# iotst.net
KiCad netlist of a schematic drawn in EAGLE
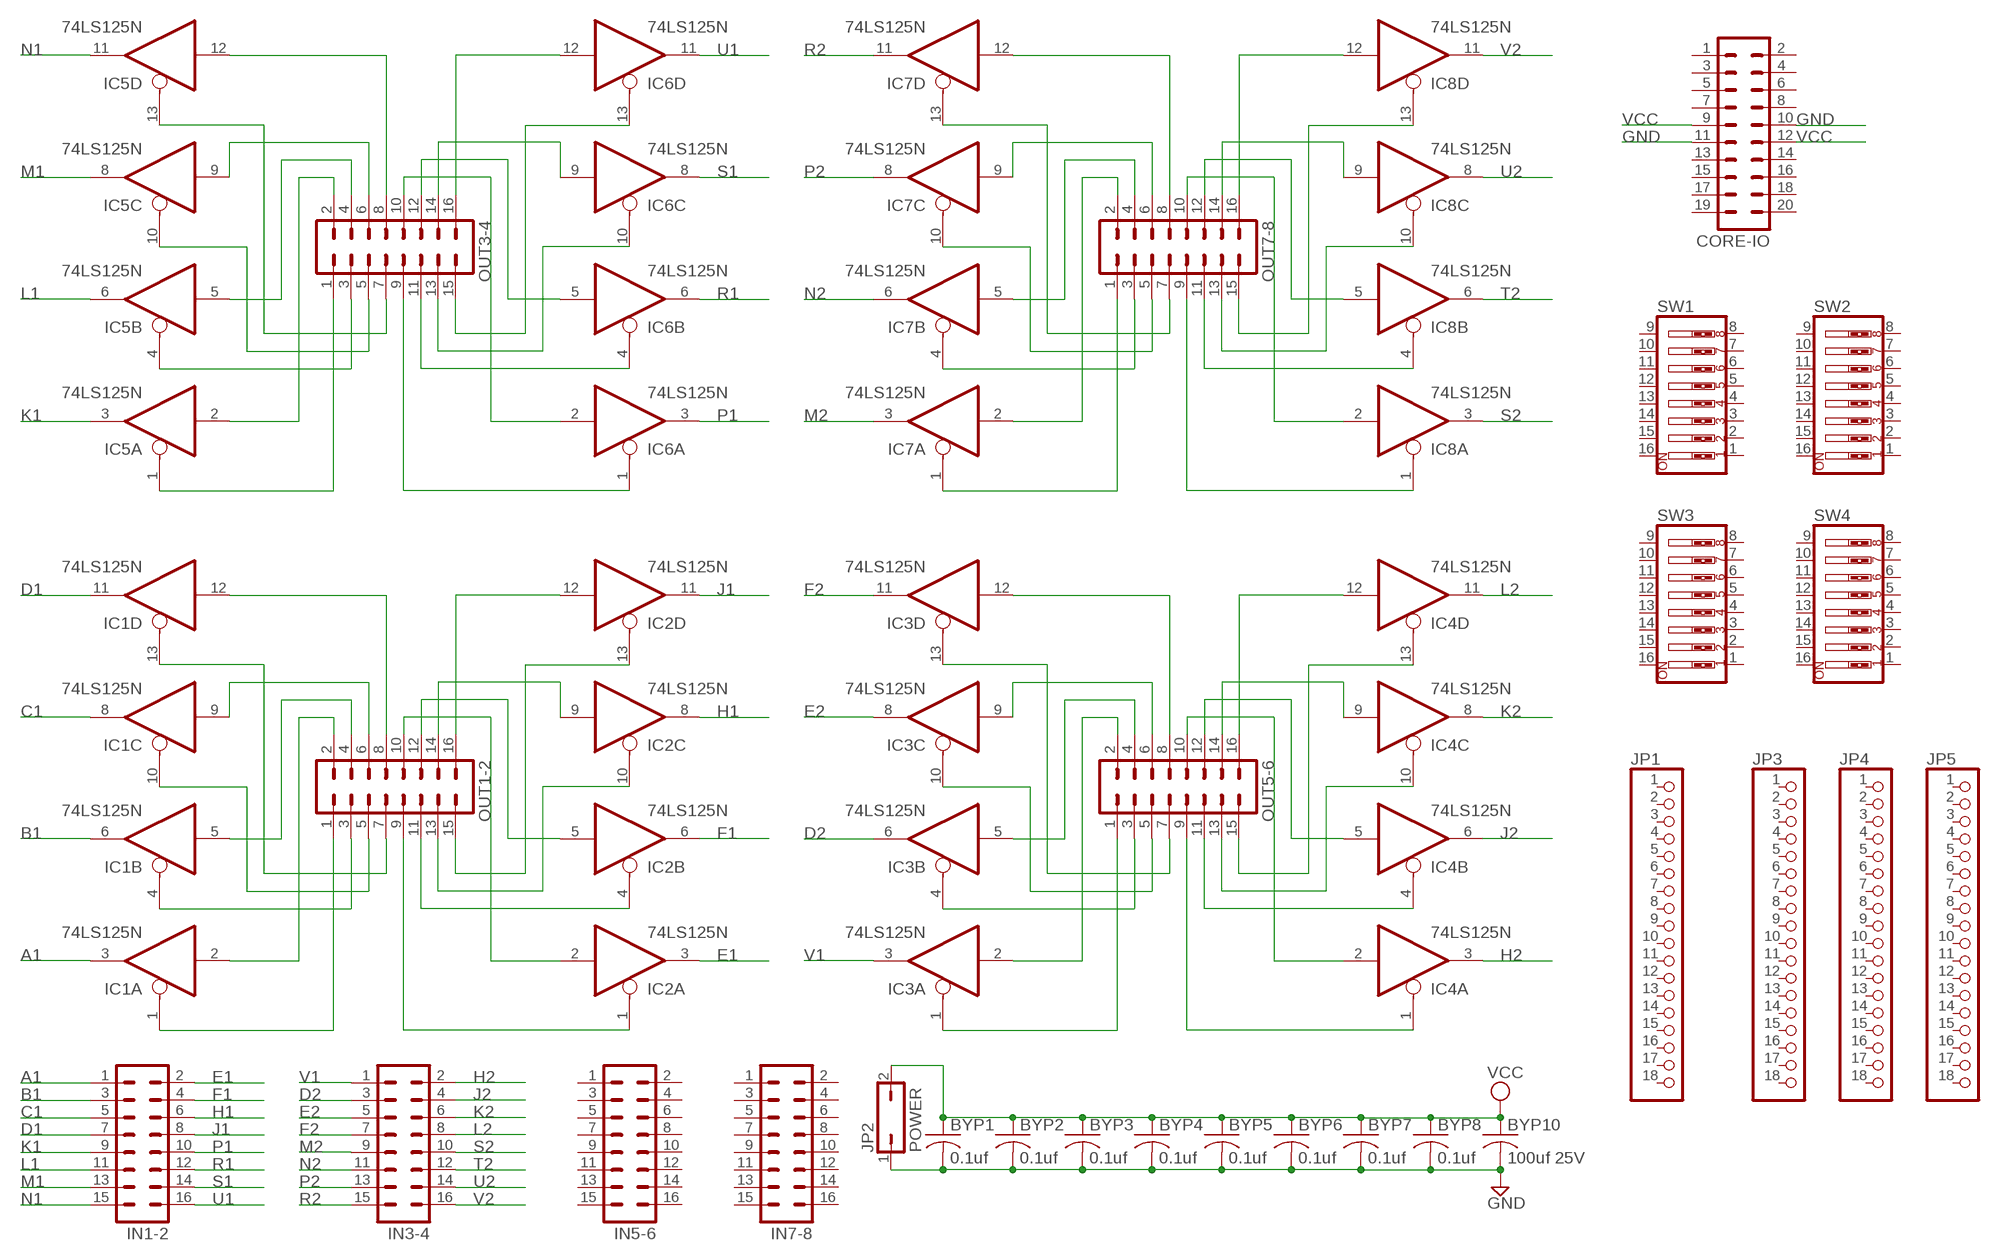
[diagram p0: schematic, sheet 1]
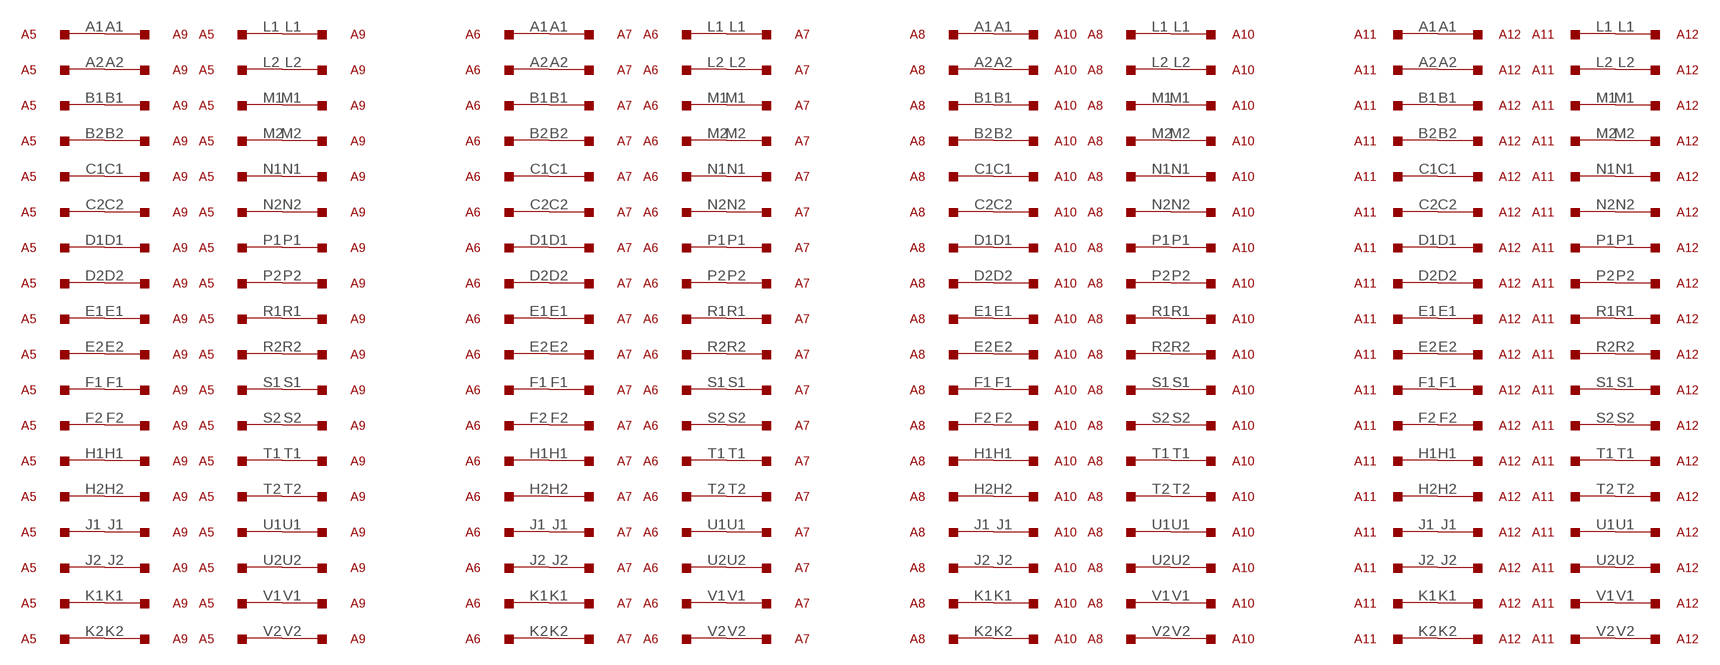
[diagram p1: schematic, sheet 2]
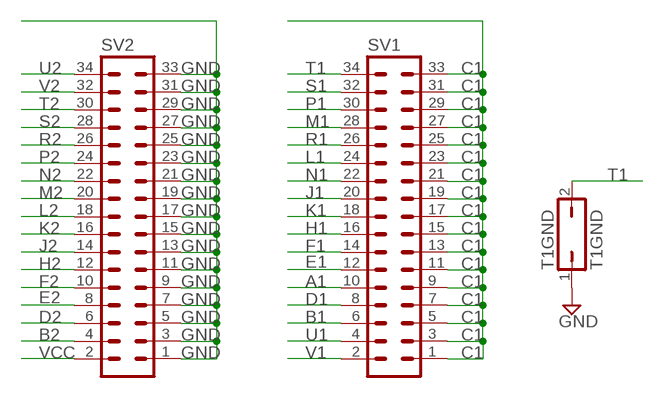
[diagram p2: schematic, sheet 3]

(export (version "E")
  (design (tool "Eeschema 10.0.6"))
  (components
    (comp (ref "A5")
      (value "M916")
      (footprint "eagle-import:H807")
      (libsource (lib "eagle-import") (part "M916"))
    )
    (comp (ref "A6")
      (value "M916")
      (footprint "eagle-import:H807")
      (libsource (lib "eagle-import") (part "M916"))
    )
    (comp (ref "A7")
      (value "M916")
      (footprint "eagle-import:H807")
      (libsource (lib "eagle-import") (part "M916"))
    )
    (comp (ref "A8")
      (value "M916")
      (footprint "eagle-import:H807")
      (libsource (lib "eagle-import") (part "M916"))
    )
    (comp (ref "A9")
      (value "M916")
      (footprint "eagle-import:H807")
      (libsource (lib "eagle-import") (part "M916"))
    )
    (comp (ref "A10")
      (value "M916")
      (footprint "eagle-import:H807")
      (libsource (lib "eagle-import") (part "M916"))
    )
    (comp (ref "A11")
      (value "M916")
      (footprint "eagle-import:H807")
      (libsource (lib "eagle-import") (part "M916"))
    )
    (comp (ref "A12")
      (value "M916")
      (footprint "eagle-import:H807")
      (libsource (lib "eagle-import") (part "M916"))
    )
    (comp (ref "BYP1")
      (value "0.1uf")
      (footprint "eagle-import:C050-025X075")
      (libsource (lib "eagle-import") (part "C-US050-025X075"))
    )
    (comp (ref "BYP2")
      (value "0.1uf")
      (footprint "eagle-import:C050-025X075")
      (libsource (lib "eagle-import") (part "C-US050-025X075"))
    )
    (comp (ref "BYP3")
      (value "0.1uf")
      (footprint "eagle-import:C050-025X075")
      (libsource (lib "eagle-import") (part "C-US050-025X075"))
    )
    (comp (ref "BYP4")
      (value "0.1uf")
      (footprint "eagle-import:C050-025X075")
      (libsource (lib "eagle-import") (part "C-US050-025X075"))
    )
    (comp (ref "BYP5")
      (value "0.1uf")
      (footprint "eagle-import:C050-025X075")
      (libsource (lib "eagle-import") (part "C-US050-025X075"))
    )
    (comp (ref "BYP6")
      (value "0.1uf")
      (footprint "eagle-import:C050-025X075")
      (libsource (lib "eagle-import") (part "C-US050-025X075"))
    )
    (comp (ref "BYP7")
      (value "0.1uf")
      (footprint "eagle-import:C050-025X075")
      (libsource (lib "eagle-import") (part "C-US050-025X075"))
    )
    (comp (ref "BYP8")
      (value "0.1uf")
      (footprint "eagle-import:C050-025X075")
      (libsource (lib "eagle-import") (part "C-US050-025X075"))
    )
    (comp (ref "BYP10")
      (value "100uf 25V")
      (footprint "eagle-import:C150-064X183")
      (libsource (lib "eagle-import") (part "C-US150-064X183"))
    )
    (comp (ref "CORE-IO")
      (value "MA10-2")
      (footprint "eagle-import:MA10-2")
      (libsource (lib "eagle-import") (part "MA10-2"))
    )
    (comp (ref "IC1")
      (value "74LS125N")
      (footprint "eagle-import:DIL14")
      (libsource (lib "eagle-import") (part "74125NLS"))
    )
    (comp (ref "IC2")
      (value "74LS125N")
      (footprint "eagle-import:DIL14")
      (libsource (lib "eagle-import") (part "74125NLS"))
    )
    (comp (ref "IC3")
      (value "74LS125N")
      (footprint "eagle-import:DIL14")
      (libsource (lib "eagle-import") (part "74125NLS"))
    )
    (comp (ref "IC4")
      (value "74LS125N")
      (footprint "eagle-import:DIL14")
      (libsource (lib "eagle-import") (part "74125NLS"))
    )
    (comp (ref "IC5")
      (value "74LS125N")
      (footprint "eagle-import:DIL14")
      (libsource (lib "eagle-import") (part "74125NLS"))
    )
    (comp (ref "IC6")
      (value "74LS125N")
      (footprint "eagle-import:DIL14")
      (libsource (lib "eagle-import") (part "74125NLS"))
    )
    (comp (ref "IC7")
      (value "74LS125N")
      (footprint "eagle-import:DIL14")
      (libsource (lib "eagle-import") (part "74125NLS"))
    )
    (comp (ref "IC8")
      (value "74LS125N")
      (footprint "eagle-import:DIL14")
      (libsource (lib "eagle-import") (part "74125NLS"))
    )
    (comp (ref "IN1-2")
      (value "MA08-2")
      (footprint "eagle-import:MA08-2")
      (libsource (lib "eagle-import") (part "MA08-2"))
    )
    (comp (ref "IN3-4")
      (value "MA08-2")
      (footprint "eagle-import:MA08-2")
      (libsource (lib "eagle-import") (part "MA08-2"))
    )
    (comp (ref "IN5-6")
      (value "MA08-2")
      (footprint "eagle-import:MA08-2")
      (libsource (lib "eagle-import") (part "MA08-2"))
    )
    (comp (ref "IN7-8")
      (value "MA08-2")
      (footprint "eagle-import:MA08-2")
      (libsource (lib "eagle-import") (part "MA08-2"))
    )
    (comp (ref "JP1")
      (value "PINHD-1X18")
      (footprint "eagle-import:1X18")
      (libsource (lib "eagle-import") (part "PINHD-1X18"))
    )
    (comp (ref "JP2")
      (value "POWER")
      (footprint "eagle-import:JP1")
      (libsource (lib "eagle-import") (part "JP1Q"))
    )
    (comp (ref "JP3")
      (value "PINHD-1X18")
      (footprint "eagle-import:1X18")
      (libsource (lib "eagle-import") (part "PINHD-1X18"))
    )
    (comp (ref "JP4")
      (value "PINHD-1X18")
      (footprint "eagle-import:1X18")
      (libsource (lib "eagle-import") (part "PINHD-1X18"))
    )
    (comp (ref "JP5")
      (value "PINHD-1X18")
      (footprint "eagle-import:1X18")
      (libsource (lib "eagle-import") (part "PINHD-1X18"))
    )
    (comp (ref "OUT1-2")
      (value "MA08-2")
      (footprint "eagle-import:MA08-2")
      (libsource (lib "eagle-import") (part "MA08-2"))
    )
    (comp (ref "OUT3-4")
      (value "MA08-2")
      (footprint "eagle-import:MA08-2")
      (libsource (lib "eagle-import") (part "MA08-2"))
    )
    (comp (ref "OUT5-6")
      (value "MA08-2")
      (footprint "eagle-import:MA08-2")
      (libsource (lib "eagle-import") (part "MA08-2"))
    )
    (comp (ref "OUT7-8")
      (value "MA08-2")
      (footprint "eagle-import:MA08-2")
      (libsource (lib "eagle-import") (part "MA08-2"))
    )
    (comp (ref "SW1")
      (value "SW_DIP-8")
      (footprint "eagle-import:EDG-08")
      (libsource (lib "eagle-import") (part "SW_DIP-8"))
    )
    (comp (ref "SW2")
      (value "SW_DIP-8")
      (footprint "eagle-import:EDG-08")
      (libsource (lib "eagle-import") (part "SW_DIP-8"))
    )
    (comp (ref "SW3")
      (value "SW_DIP-8")
      (footprint "eagle-import:EDG-08")
      (libsource (lib "eagle-import") (part "SW_DIP-8"))
    )
    (comp (ref "SW4")
      (value "SW_DIP-8")
      (footprint "eagle-import:EDG-08")
      (libsource (lib "eagle-import") (part "SW_DIP-8"))
    )
    (comp (ref "SV1")
      (value "MA17-2")
      (footprint "eagle-import:MA17-2")
      (libsource (lib "eagle-import") (part "MA17-2"))
    )
    (comp (ref "SV2")
      (value "MA17-2")
      (footprint "eagle-import:MA17-2")
      (libsource (lib "eagle-import") (part "MA17-2"))
    )
    (comp (ref "T1GND")
      (value "T1GND")
      (footprint "eagle-import:JP1")
      (libsource (lib "eagle-import") (part "JP1Q"))
    )
  )
  (nets
    (net (code "1") (name "A1") (class "Default")
      (node (ref "IC1") (pin "3") (pinfunction "O_3") (pintype "tri_state"))
      (node (ref "IN1-2") (pin "1") (pinfunction "1_1") (pintype "passive"))
      (node (ref "SV1") (pin "10") (pinfunction "10_10") (pintype "passive"))
    )
    (net (code "2") (name "B1") (class "Default")
      (node (ref "IC1") (pin "6") (pinfunction "O_6") (pintype "tri_state"))
      (node (ref "IN1-2") (pin "3") (pinfunction "3_3") (pintype "passive"))
      (node (ref "SV1") (pin "6") (pinfunction "6_6") (pintype "passive"))
    )
    (net (code "3") (name "B2") (class "Default")
      (node (ref "SV2") (pin "4") (pinfunction "4_4") (pintype "passive"))
    )
    (net (code "4") (name "C1") (class "Default")
      (node (ref "IC1") (pin "8") (pinfunction "O_8") (pintype "tri_state"))
      (node (ref "IN1-2") (pin "5") (pinfunction "5_5") (pintype "passive"))
      (node (ref "SV1") (pin "1") (pinfunction "1_1") (pintype "passive"))
      (node (ref "SV1") (pin "11") (pinfunction "11_11") (pintype "passive"))
      (node (ref "SV1") (pin "13") (pinfunction "13_13") (pintype "passive"))
      (node (ref "SV1") (pin "15") (pinfunction "15_15") (pintype "passive"))
      (node (ref "SV1") (pin "17") (pinfunction "17_17") (pintype "passive"))
      (node (ref "SV1") (pin "19") (pinfunction "19_19") (pintype "passive"))
      (node (ref "SV1") (pin "21") (pinfunction "21_21") (pintype "passive"))
      (node (ref "SV1") (pin "23") (pinfunction "23_23") (pintype "passive"))
      (node (ref "SV1") (pin "25") (pinfunction "25_25") (pintype "passive"))
      (node (ref "SV1") (pin "27") (pinfunction "27_27") (pintype "passive"))
      (node (ref "SV1") (pin "29") (pinfunction "29_29") (pintype "passive"))
      (node (ref "SV1") (pin "3") (pinfunction "3_3") (pintype "passive"))
      (node (ref "SV1") (pin "31") (pinfunction "31_31") (pintype "passive"))
      (node (ref "SV1") (pin "33") (pinfunction "33_33") (pintype "passive"))
      (node (ref "SV1") (pin "5") (pinfunction "5_5") (pintype "passive"))
      (node (ref "SV1") (pin "7") (pinfunction "7_7") (pintype "passive"))
      (node (ref "SV1") (pin "9") (pinfunction "9_9") (pintype "passive"))
    )
    (net (code "5") (name "D1") (class "Default")
      (node (ref "IC1") (pin "11") (pinfunction "O_11") (pintype "tri_state"))
      (node (ref "IN1-2") (pin "7") (pinfunction "7_7") (pintype "passive"))
      (node (ref "SV1") (pin "8") (pinfunction "8_8") (pintype "passive"))
    )
    (net (code "6") (name "D2") (class "Default")
      (node (ref "IC3") (pin "6") (pinfunction "O_6") (pintype "tri_state"))
      (node (ref "IN3-4") (pin "3") (pinfunction "3_3") (pintype "passive"))
      (node (ref "SV2") (pin "6") (pinfunction "6_6") (pintype "passive"))
    )
    (net (code "7") (name "E1") (class "Default")
      (node (ref "IC2") (pin "3") (pinfunction "O_3") (pintype "tri_state"))
      (node (ref "IN1-2") (pin "2") (pinfunction "2_2") (pintype "passive"))
      (node (ref "SV1") (pin "12") (pinfunction "12_12") (pintype "passive"))
    )
    (net (code "8") (name "E2") (class "Default")
      (node (ref "IC3") (pin "8") (pinfunction "O_8") (pintype "tri_state"))
      (node (ref "IN3-4") (pin "5") (pinfunction "5_5") (pintype "passive"))
      (node (ref "SV2") (pin "8") (pinfunction "8_8") (pintype "passive"))
    )
    (net (code "9") (name "F1") (class "Default")
      (node (ref "IC2") (pin "6") (pinfunction "O_6") (pintype "tri_state"))
      (node (ref "IN1-2") (pin "4") (pinfunction "4_4") (pintype "passive"))
      (node (ref "SV1") (pin "14") (pinfunction "14_14") (pintype "passive"))
    )
    (net (code "10") (name "F2") (class "Default")
      (node (ref "IC3") (pin "11") (pinfunction "O_11") (pintype "tri_state"))
      (node (ref "IN3-4") (pin "7") (pinfunction "7_7") (pintype "passive"))
      (node (ref "SV2") (pin "10") (pinfunction "10_10") (pintype "passive"))
    )
    (net (code "11") (name "GND") (class "Default")
      (node (ref "BYP1") (pin "2") (pinfunction "2_2") (pintype "passive"))
      (node (ref "BYP10") (pin "2") (pinfunction "2_2") (pintype "passive"))
      (node (ref "BYP2") (pin "2") (pinfunction "2_2") (pintype "passive"))
      (node (ref "BYP3") (pin "2") (pinfunction "2_2") (pintype "passive"))
      (node (ref "BYP4") (pin "2") (pinfunction "2_2") (pintype "passive"))
      (node (ref "BYP5") (pin "2") (pinfunction "2_2") (pintype "passive"))
      (node (ref "BYP6") (pin "2") (pinfunction "2_2") (pintype "passive"))
      (node (ref "BYP7") (pin "2") (pinfunction "2_2") (pintype "passive"))
      (node (ref "BYP8") (pin "2") (pinfunction "2_2") (pintype "passive"))
      (node (ref "CORE-IO") (pin "10") (pinfunction "10_10") (pintype "passive"))
      (node (ref "CORE-IO") (pin "11") (pinfunction "11_11") (pintype "passive"))
      (node (ref "JP2") (pin "1") (pinfunction "1_1") (pintype "passive"))
      (node (ref "SV2") (pin "1") (pinfunction "1_1") (pintype "passive"))
      (node (ref "SV2") (pin "11") (pinfunction "11_11") (pintype "passive"))
      (node (ref "SV2") (pin "13") (pinfunction "13_13") (pintype "passive"))
      (node (ref "SV2") (pin "15") (pinfunction "15_15") (pintype "passive"))
      (node (ref "SV2") (pin "17") (pinfunction "17_17") (pintype "passive"))
      (node (ref "SV2") (pin "19") (pinfunction "19_19") (pintype "passive"))
      (node (ref "SV2") (pin "21") (pinfunction "21_21") (pintype "passive"))
      (node (ref "SV2") (pin "23") (pinfunction "23_23") (pintype "passive"))
      (node (ref "SV2") (pin "25") (pinfunction "25_25") (pintype "passive"))
      (node (ref "SV2") (pin "27") (pinfunction "27_27") (pintype "passive"))
      (node (ref "SV2") (pin "29") (pinfunction "29_29") (pintype "passive"))
      (node (ref "SV2") (pin "3") (pinfunction "3_3") (pintype "passive"))
      (node (ref "SV2") (pin "31") (pinfunction "31_31") (pintype "passive"))
      (node (ref "SV2") (pin "33") (pinfunction "33_33") (pintype "passive"))
      (node (ref "SV2") (pin "5") (pinfunction "5_5") (pintype "passive"))
      (node (ref "SV2") (pin "7") (pinfunction "7_7") (pintype "passive"))
      (node (ref "SV2") (pin "9") (pinfunction "9_9") (pintype "passive"))
      (node (ref "T1GND") (pin "1") (pinfunction "1_1") (pintype "passive"))
    )
    (net (code "12") (name "H1") (class "Default")
      (node (ref "IC2") (pin "8") (pinfunction "O_8") (pintype "tri_state"))
      (node (ref "IN1-2") (pin "6") (pinfunction "6_6") (pintype "passive"))
      (node (ref "SV1") (pin "16") (pinfunction "16_16") (pintype "passive"))
    )
    (net (code "13") (name "H2") (class "Default")
      (node (ref "IC4") (pin "3") (pinfunction "O_3") (pintype "tri_state"))
      (node (ref "IN3-4") (pin "2") (pinfunction "2_2") (pintype "passive"))
      (node (ref "SV2") (pin "12") (pinfunction "12_12") (pintype "passive"))
    )
    (net (code "14") (name "J1") (class "Default")
      (node (ref "IC2") (pin "11") (pinfunction "O_11") (pintype "tri_state"))
      (node (ref "IN1-2") (pin "8") (pinfunction "8_8") (pintype "passive"))
      (node (ref "SV1") (pin "20") (pinfunction "20_20") (pintype "passive"))
    )
    (net (code "15") (name "J2") (class "Default")
      (node (ref "IC4") (pin "6") (pinfunction "O_6") (pintype "tri_state"))
      (node (ref "IN3-4") (pin "4") (pinfunction "4_4") (pintype "passive"))
      (node (ref "SV2") (pin "14") (pinfunction "14_14") (pintype "passive"))
    )
    (net (code "16") (name "K1") (class "Default")
      (node (ref "IC5") (pin "3") (pinfunction "O_3") (pintype "tri_state"))
      (node (ref "IN1-2") (pin "9") (pinfunction "9_9") (pintype "passive"))
      (node (ref "SV1") (pin "18") (pinfunction "18_18") (pintype "passive"))
    )
    (net (code "17") (name "K2") (class "Default")
      (node (ref "IC4") (pin "8") (pinfunction "O_8") (pintype "tri_state"))
      (node (ref "IN3-4") (pin "6") (pinfunction "6_6") (pintype "passive"))
      (node (ref "SV2") (pin "16") (pinfunction "16_16") (pintype "passive"))
    )
    (net (code "18") (name "L1") (class "Default")
      (node (ref "IC5") (pin "6") (pinfunction "O_6") (pintype "tri_state"))
      (node (ref "IN1-2") (pin "11") (pinfunction "11_11") (pintype "passive"))
      (node (ref "SV1") (pin "24") (pinfunction "24_24") (pintype "passive"))
    )
    (net (code "19") (name "L2") (class "Default")
      (node (ref "IC4") (pin "11") (pinfunction "O_11") (pintype "tri_state"))
      (node (ref "IN3-4") (pin "8") (pinfunction "8_8") (pintype "passive"))
      (node (ref "SV2") (pin "18") (pinfunction "18_18") (pintype "passive"))
    )
    (net (code "20") (name "M1") (class "Default")
      (node (ref "IC5") (pin "8") (pinfunction "O_8") (pintype "tri_state"))
      (node (ref "IN1-2") (pin "13") (pinfunction "13_13") (pintype "passive"))
      (node (ref "SV1") (pin "28") (pinfunction "28_28") (pintype "passive"))
    )
    (net (code "21") (name "M2") (class "Default")
      (node (ref "IC7") (pin "3") (pinfunction "O_3") (pintype "tri_state"))
      (node (ref "IN3-4") (pin "9") (pinfunction "9_9") (pintype "passive"))
      (node (ref "SV2") (pin "20") (pinfunction "20_20") (pintype "passive"))
    )
    (net (code "22") (name "N1") (class "Default")
      (node (ref "IC5") (pin "11") (pinfunction "O_11") (pintype "tri_state"))
      (node (ref "IN1-2") (pin "15") (pinfunction "15_15") (pintype "passive"))
      (node (ref "SV1") (pin "22") (pinfunction "22_22") (pintype "passive"))
    )
    (net (code "23") (name "N2") (class "Default")
      (node (ref "IC7") (pin "6") (pinfunction "O_6") (pintype "tri_state"))
      (node (ref "IN3-4") (pin "11") (pinfunction "11_11") (pintype "passive"))
      (node (ref "SV2") (pin "22") (pinfunction "22_22") (pintype "passive"))
    )
    (net (code "24") (name "Net-(A5A-P$2)") (class "Default")
      (node (ref "A5") (pin "A1") (pinfunction "P$2_A1") (pintype "bidirectional"))
      (node (ref "A9") (pin "A1") (pinfunction "P$2_A1") (pintype "bidirectional"))
    )
    (net (code "25") (name "Net-(A5AA-P$2)") (class "Default")
      (node (ref "A5") (pin "R1") (pinfunction "P$2_R1") (pintype "bidirectional"))
      (node (ref "A9") (pin "R1") (pinfunction "P$2_R1") (pintype "bidirectional"))
    )
    (net (code "26") (name "Net-(A5AB-P$2)") (class "Default")
      (node (ref "A5") (pin "R2") (pinfunction "P$2_R2") (pintype "bidirectional"))
      (node (ref "A9") (pin "R2") (pinfunction "P$2_R2") (pintype "bidirectional"))
    )
    (net (code "27") (name "Net-(A5AC-P$2)") (class "Default")
      (node (ref "A5") (pin "S1") (pinfunction "P$2_S1") (pintype "bidirectional"))
      (node (ref "A9") (pin "S1") (pinfunction "P$2_S1") (pintype "bidirectional"))
    )
    (net (code "28") (name "Net-(A5AD-P$2)") (class "Default")
      (node (ref "A5") (pin "S2") (pinfunction "P$2_S2") (pintype "bidirectional"))
      (node (ref "A9") (pin "S2") (pinfunction "P$2_S2") (pintype "bidirectional"))
    )
    (net (code "29") (name "Net-(A5AE-P$2)") (class "Default")
      (node (ref "A5") (pin "T1") (pinfunction "P$2_T1") (pintype "bidirectional"))
      (node (ref "A9") (pin "T1") (pinfunction "P$2_T1") (pintype "bidirectional"))
    )
    (net (code "30") (name "Net-(A5AF-P$2)") (class "Default")
      (node (ref "A5") (pin "T2") (pinfunction "P$2_T2") (pintype "bidirectional"))
      (node (ref "A9") (pin "T2") (pinfunction "P$2_T2") (pintype "bidirectional"))
    )
    (net (code "31") (name "Net-(A5AG-P$2)") (class "Default")
      (node (ref "A5") (pin "U1") (pinfunction "P$2_U1") (pintype "bidirectional"))
      (node (ref "A9") (pin "U1") (pinfunction "P$2_U1") (pintype "bidirectional"))
    )
    (net (code "32") (name "Net-(A5AH-P$2)") (class "Default")
      (node (ref "A5") (pin "U2") (pinfunction "P$2_U2") (pintype "bidirectional"))
      (node (ref "A9") (pin "U2") (pinfunction "P$2_U2") (pintype "bidirectional"))
    )
    (net (code "33") (name "Net-(A5AI-P$2)") (class "Default")
      (node (ref "A5") (pin "V1") (pinfunction "P$2_V1") (pintype "bidirectional"))
      (node (ref "A9") (pin "V1") (pinfunction "P$2_V1") (pintype "bidirectional"))
    )
    (net (code "34") (name "Net-(A5AJ-P$2)") (class "Default")
      (node (ref "A5") (pin "V2") (pinfunction "P$2_V2") (pintype "bidirectional"))
      (node (ref "A9") (pin "V2") (pinfunction "P$2_V2") (pintype "bidirectional"))
    )
    (net (code "35") (name "Net-(A5B-P$2)") (class "Default")
      (node (ref "A5") (pin "A2") (pinfunction "P$2_A2") (pintype "bidirectional"))
      (node (ref "A9") (pin "A2") (pinfunction "P$2_A2") (pintype "bidirectional"))
    )
    (net (code "36") (name "Net-(A5C-P$2)") (class "Default")
      (node (ref "A5") (pin "B1") (pinfunction "P$2_B1") (pintype "bidirectional"))
      (node (ref "A9") (pin "B1") (pinfunction "P$2_B1") (pintype "bidirectional"))
    )
    (net (code "37") (name "Net-(A5D-P$2)") (class "Default")
      (node (ref "A5") (pin "B2") (pinfunction "P$2_B2") (pintype "bidirectional"))
      (node (ref "A9") (pin "B2") (pinfunction "P$2_B2") (pintype "bidirectional"))
    )
    (net (code "38") (name "Net-(A5E-P$2)") (class "Default")
      (node (ref "A5") (pin "C1") (pinfunction "P$2_C1") (pintype "bidirectional"))
      (node (ref "A9") (pin "C1") (pinfunction "P$2_C1") (pintype "bidirectional"))
    )
    (net (code "39") (name "Net-(A5F-P$2)") (class "Default")
      (node (ref "A5") (pin "C2") (pinfunction "P$2_C2") (pintype "bidirectional"))
      (node (ref "A9") (pin "C2") (pinfunction "P$2_C2") (pintype "bidirectional"))
    )
    (net (code "40") (name "Net-(A5G-P$2)") (class "Default")
      (node (ref "A5") (pin "D1") (pinfunction "P$2_D1") (pintype "bidirectional"))
      (node (ref "A9") (pin "D1") (pinfunction "P$2_D1") (pintype "bidirectional"))
    )
    (net (code "41") (name "Net-(A5H-P$2)") (class "Default")
      (node (ref "A5") (pin "D2") (pinfunction "P$2_D2") (pintype "bidirectional"))
      (node (ref "A9") (pin "D2") (pinfunction "P$2_D2") (pintype "bidirectional"))
    )
    (net (code "42") (name "Net-(A5I-P$2)") (class "Default")
      (node (ref "A5") (pin "E1") (pinfunction "P$2_E1") (pintype "bidirectional"))
      (node (ref "A9") (pin "E1") (pinfunction "P$2_E1") (pintype "bidirectional"))
    )
    (net (code "43") (name "Net-(A5J-P$2)") (class "Default")
      (node (ref "A5") (pin "E2") (pinfunction "P$2_E2") (pintype "bidirectional"))
      (node (ref "A9") (pin "E2") (pinfunction "P$2_E2") (pintype "bidirectional"))
    )
    (net (code "44") (name "Net-(A5K-P$2)") (class "Default")
      (node (ref "A5") (pin "F1") (pinfunction "P$2_F1") (pintype "bidirectional"))
      (node (ref "A9") (pin "F1") (pinfunction "P$2_F1") (pintype "bidirectional"))
    )
    (net (code "45") (name "Net-(A5L-P$2)") (class "Default")
      (node (ref "A5") (pin "F2") (pinfunction "P$2_F2") (pintype "bidirectional"))
      (node (ref "A9") (pin "F2") (pinfunction "P$2_F2") (pintype "bidirectional"))
    )
    (net (code "46") (name "Net-(A5M-P$2)") (class "Default")
      (node (ref "A5") (pin "H1") (pinfunction "P$2_H1") (pintype "bidirectional"))
      (node (ref "A9") (pin "H1") (pinfunction "P$2_H1") (pintype "bidirectional"))
    )
    (net (code "47") (name "Net-(A5N-P$2)") (class "Default")
      (node (ref "A5") (pin "H2") (pinfunction "P$2_H2") (pintype "bidirectional"))
      (node (ref "A9") (pin "H2") (pinfunction "P$2_H2") (pintype "bidirectional"))
    )
    (net (code "48") (name "Net-(A5O-P$2)") (class "Default")
      (node (ref "A5") (pin "J1") (pinfunction "P$2_J1") (pintype "bidirectional"))
      (node (ref "A9") (pin "J1") (pinfunction "P$2_J1") (pintype "bidirectional"))
    )
    (net (code "49") (name "Net-(A5P-P$2)") (class "Default")
      (node (ref "A5") (pin "J2") (pinfunction "P$2_J2") (pintype "bidirectional"))
      (node (ref "A9") (pin "J2") (pinfunction "P$2_J2") (pintype "bidirectional"))
    )
    (net (code "50") (name "Net-(A5Q-P$2)") (class "Default")
      (node (ref "A5") (pin "K1") (pinfunction "P$2_K1") (pintype "bidirectional"))
      (node (ref "A9") (pin "K1") (pinfunction "P$2_K1") (pintype "bidirectional"))
    )
    (net (code "51") (name "Net-(A5R-P$2)") (class "Default")
      (node (ref "A5") (pin "K2") (pinfunction "P$2_K2") (pintype "bidirectional"))
      (node (ref "A9") (pin "K2") (pinfunction "P$2_K2") (pintype "bidirectional"))
    )
    (net (code "52") (name "Net-(A5S-P$2)") (class "Default")
      (node (ref "A5") (pin "L1") (pinfunction "P$2_L1") (pintype "bidirectional"))
      (node (ref "A9") (pin "L1") (pinfunction "P$2_L1") (pintype "bidirectional"))
    )
    (net (code "53") (name "Net-(A5T-P$2)") (class "Default")
      (node (ref "A5") (pin "L2") (pinfunction "P$2_L2") (pintype "bidirectional"))
      (node (ref "A9") (pin "L2") (pinfunction "P$2_L2") (pintype "bidirectional"))
    )
    (net (code "54") (name "Net-(A5U-P$2)") (class "Default")
      (node (ref "A5") (pin "M1") (pinfunction "P$2_M1") (pintype "bidirectional"))
      (node (ref "A9") (pin "M1") (pinfunction "P$2_M1") (pintype "bidirectional"))
    )
    (net (code "55") (name "Net-(A5V-P$2)") (class "Default")
      (node (ref "A5") (pin "M2") (pinfunction "P$2_M2") (pintype "bidirectional"))
      (node (ref "A9") (pin "M2") (pinfunction "P$2_M2") (pintype "bidirectional"))
    )
    (net (code "56") (name "Net-(A5W-P$2)") (class "Default")
      (node (ref "A5") (pin "N1") (pinfunction "P$2_N1") (pintype "bidirectional"))
      (node (ref "A9") (pin "N1") (pinfunction "P$2_N1") (pintype "bidirectional"))
    )
    (net (code "57") (name "Net-(A5X-P$2)") (class "Default")
      (node (ref "A5") (pin "N2") (pinfunction "P$2_N2") (pintype "bidirectional"))
      (node (ref "A9") (pin "N2") (pinfunction "P$2_N2") (pintype "bidirectional"))
    )
    (net (code "58") (name "Net-(A5Y-P$2)") (class "Default")
      (node (ref "A5") (pin "P1") (pinfunction "P$2_P1") (pintype "bidirectional"))
      (node (ref "A9") (pin "P1") (pinfunction "P$2_P1") (pintype "bidirectional"))
    )
    (net (code "59") (name "Net-(A5Z-P$2)") (class "Default")
      (node (ref "A5") (pin "P2") (pinfunction "P$2_P2") (pintype "bidirectional"))
      (node (ref "A9") (pin "P2") (pinfunction "P$2_P2") (pintype "bidirectional"))
    )
    (net (code "60") (name "Net-(A6A-P$2)") (class "Default")
      (node (ref "A6") (pin "A1") (pinfunction "P$2_A1") (pintype "bidirectional"))
      (node (ref "A7") (pin "A1") (pinfunction "P$2_A1") (pintype "bidirectional"))
    )
    (net (code "61") (name "Net-(A6AA-P$2)") (class "Default")
      (node (ref "A6") (pin "R1") (pinfunction "P$2_R1") (pintype "bidirectional"))
      (node (ref "A7") (pin "R1") (pinfunction "P$2_R1") (pintype "bidirectional"))
    )
    (net (code "62") (name "Net-(A6AB-P$2)") (class "Default")
      (node (ref "A6") (pin "R2") (pinfunction "P$2_R2") (pintype "bidirectional"))
      (node (ref "A7") (pin "R2") (pinfunction "P$2_R2") (pintype "bidirectional"))
    )
    (net (code "63") (name "Net-(A6AC-P$2)") (class "Default")
      (node (ref "A6") (pin "S1") (pinfunction "P$2_S1") (pintype "bidirectional"))
      (node (ref "A7") (pin "S1") (pinfunction "P$2_S1") (pintype "bidirectional"))
    )
    (net (code "64") (name "Net-(A6AD-P$2)") (class "Default")
      (node (ref "A6") (pin "S2") (pinfunction "P$2_S2") (pintype "bidirectional"))
      (node (ref "A7") (pin "S2") (pinfunction "P$2_S2") (pintype "bidirectional"))
    )
    (net (code "65") (name "Net-(A6AE-P$2)") (class "Default")
      (node (ref "A6") (pin "T1") (pinfunction "P$2_T1") (pintype "bidirectional"))
      (node (ref "A7") (pin "T1") (pinfunction "P$2_T1") (pintype "bidirectional"))
    )
    (net (code "66") (name "Net-(A6AF-P$2)") (class "Default")
      (node (ref "A6") (pin "T2") (pinfunction "P$2_T2") (pintype "bidirectional"))
      (node (ref "A7") (pin "T2") (pinfunction "P$2_T2") (pintype "bidirectional"))
    )
    (net (code "67") (name "Net-(A6AG-P$2)") (class "Default")
      (node (ref "A6") (pin "U1") (pinfunction "P$2_U1") (pintype "bidirectional"))
      (node (ref "A7") (pin "U1") (pinfunction "P$2_U1") (pintype "bidirectional"))
    )
    (net (code "68") (name "Net-(A6AH-P$2)") (class "Default")
      (node (ref "A6") (pin "U2") (pinfunction "P$2_U2") (pintype "bidirectional"))
      (node (ref "A7") (pin "U2") (pinfunction "P$2_U2") (pintype "bidirectional"))
    )
    (net (code "69") (name "Net-(A6AI-P$2)") (class "Default")
      (node (ref "A6") (pin "V1") (pinfunction "P$2_V1") (pintype "bidirectional"))
      (node (ref "A7") (pin "V1") (pinfunction "P$2_V1") (pintype "bidirectional"))
    )
    (net (code "70") (name "Net-(A6AJ-P$2)") (class "Default")
      (node (ref "A6") (pin "V2") (pinfunction "P$2_V2") (pintype "bidirectional"))
      (node (ref "A7") (pin "V2") (pinfunction "P$2_V2") (pintype "bidirectional"))
    )
    (net (code "71") (name "Net-(A6B-P$2)") (class "Default")
      (node (ref "A6") (pin "A2") (pinfunction "P$2_A2") (pintype "bidirectional"))
      (node (ref "A7") (pin "A2") (pinfunction "P$2_A2") (pintype "bidirectional"))
    )
    (net (code "72") (name "Net-(A6C-P$2)") (class "Default")
      (node (ref "A6") (pin "B1") (pinfunction "P$2_B1") (pintype "bidirectional"))
      (node (ref "A7") (pin "B1") (pinfunction "P$2_B1") (pintype "bidirectional"))
    )
    (net (code "73") (name "Net-(A6D-P$2)") (class "Default")
      (node (ref "A6") (pin "B2") (pinfunction "P$2_B2") (pintype "bidirectional"))
      (node (ref "A7") (pin "B2") (pinfunction "P$2_B2") (pintype "bidirectional"))
    )
    (net (code "74") (name "Net-(A6E-P$2)") (class "Default")
      (node (ref "A6") (pin "C1") (pinfunction "P$2_C1") (pintype "bidirectional"))
      (node (ref "A7") (pin "C1") (pinfunction "P$2_C1") (pintype "bidirectional"))
    )
    (net (code "75") (name "Net-(A6F-P$2)") (class "Default")
      (node (ref "A6") (pin "C2") (pinfunction "P$2_C2") (pintype "bidirectional"))
      (node (ref "A7") (pin "C2") (pinfunction "P$2_C2") (pintype "bidirectional"))
    )
    (net (code "76") (name "Net-(A6G-P$2)") (class "Default")
      (node (ref "A6") (pin "D1") (pinfunction "P$2_D1") (pintype "bidirectional"))
      (node (ref "A7") (pin "D1") (pinfunction "P$2_D1") (pintype "bidirectional"))
    )
    (net (code "77") (name "Net-(A6H-P$2)") (class "Default")
      (node (ref "A6") (pin "D2") (pinfunction "P$2_D2") (pintype "bidirectional"))
      (node (ref "A7") (pin "D2") (pinfunction "P$2_D2") (pintype "bidirectional"))
    )
    (net (code "78") (name "Net-(A6I-P$2)") (class "Default")
      (node (ref "A6") (pin "E1") (pinfunction "P$2_E1") (pintype "bidirectional"))
      (node (ref "A7") (pin "E1") (pinfunction "P$2_E1") (pintype "bidirectional"))
    )
    (net (code "79") (name "Net-(A6J-P$2)") (class "Default")
      (node (ref "A6") (pin "E2") (pinfunction "P$2_E2") (pintype "bidirectional"))
      (node (ref "A7") (pin "E2") (pinfunction "P$2_E2") (pintype "bidirectional"))
    )
    (net (code "80") (name "Net-(A6K-P$2)") (class "Default")
      (node (ref "A6") (pin "F1") (pinfunction "P$2_F1") (pintype "bidirectional"))
      (node (ref "A7") (pin "F1") (pinfunction "P$2_F1") (pintype "bidirectional"))
    )
    (net (code "81") (name "Net-(A6L-P$2)") (class "Default")
      (node (ref "A6") (pin "F2") (pinfunction "P$2_F2") (pintype "bidirectional"))
      (node (ref "A7") (pin "F2") (pinfunction "P$2_F2") (pintype "bidirectional"))
    )
    (net (code "82") (name "Net-(A6M-P$2)") (class "Default")
      (node (ref "A6") (pin "H1") (pinfunction "P$2_H1") (pintype "bidirectional"))
      (node (ref "A7") (pin "H1") (pinfunction "P$2_H1") (pintype "bidirectional"))
    )
    (net (code "83") (name "Net-(A6N-P$2)") (class "Default")
      (node (ref "A6") (pin "H2") (pinfunction "P$2_H2") (pintype "bidirectional"))
      (node (ref "A7") (pin "H2") (pinfunction "P$2_H2") (pintype "bidirectional"))
    )
    (net (code "84") (name "Net-(A6O-P$2)") (class "Default")
      (node (ref "A6") (pin "J1") (pinfunction "P$2_J1") (pintype "bidirectional"))
      (node (ref "A7") (pin "J1") (pinfunction "P$2_J1") (pintype "bidirectional"))
    )
    (net (code "85") (name "Net-(A6P-P$2)") (class "Default")
      (node (ref "A6") (pin "J2") (pinfunction "P$2_J2") (pintype "bidirectional"))
      (node (ref "A7") (pin "J2") (pinfunction "P$2_J2") (pintype "bidirectional"))
    )
    (net (code "86") (name "Net-(A6Q-P$2)") (class "Default")
      (node (ref "A6") (pin "K1") (pinfunction "P$2_K1") (pintype "bidirectional"))
      (node (ref "A7") (pin "K1") (pinfunction "P$2_K1") (pintype "bidirectional"))
    )
    (net (code "87") (name "Net-(A6R-P$2)") (class "Default")
      (node (ref "A6") (pin "K2") (pinfunction "P$2_K2") (pintype "bidirectional"))
      (node (ref "A7") (pin "K2") (pinfunction "P$2_K2") (pintype "bidirectional"))
    )
    (net (code "88") (name "Net-(A6S-P$2)") (class "Default")
      (node (ref "A6") (pin "L1") (pinfunction "P$2_L1") (pintype "bidirectional"))
      (node (ref "A7") (pin "L1") (pinfunction "P$2_L1") (pintype "bidirectional"))
    )
    (net (code "89") (name "Net-(A6T-P$2)") (class "Default")
      (node (ref "A6") (pin "L2") (pinfunction "P$2_L2") (pintype "bidirectional"))
      (node (ref "A7") (pin "L2") (pinfunction "P$2_L2") (pintype "bidirectional"))
    )
    (net (code "90") (name "Net-(A6U-P$2)") (class "Default")
      (node (ref "A6") (pin "M1") (pinfunction "P$2_M1") (pintype "bidirectional"))
      (node (ref "A7") (pin "M1") (pinfunction "P$2_M1") (pintype "bidirectional"))
    )
    (net (code "91") (name "Net-(A6V-P$2)") (class "Default")
      (node (ref "A6") (pin "M2") (pinfunction "P$2_M2") (pintype "bidirectional"))
      (node (ref "A7") (pin "M2") (pinfunction "P$2_M2") (pintype "bidirectional"))
    )
    (net (code "92") (name "Net-(A6W-P$2)") (class "Default")
      (node (ref "A6") (pin "N1") (pinfunction "P$2_N1") (pintype "bidirectional"))
      (node (ref "A7") (pin "N1") (pinfunction "P$2_N1") (pintype "bidirectional"))
    )
    (net (code "93") (name "Net-(A6X-P$2)") (class "Default")
      (node (ref "A6") (pin "N2") (pinfunction "P$2_N2") (pintype "bidirectional"))
      (node (ref "A7") (pin "N2") (pinfunction "P$2_N2") (pintype "bidirectional"))
    )
    (net (code "94") (name "Net-(A6Y-P$2)") (class "Default")
      (node (ref "A6") (pin "P1") (pinfunction "P$2_P1") (pintype "bidirectional"))
      (node (ref "A7") (pin "P1") (pinfunction "P$2_P1") (pintype "bidirectional"))
    )
    (net (code "95") (name "Net-(A6Z-P$2)") (class "Default")
      (node (ref "A6") (pin "P2") (pinfunction "P$2_P2") (pintype "bidirectional"))
      (node (ref "A7") (pin "P2") (pinfunction "P$2_P2") (pintype "bidirectional"))
    )
    (net (code "96") (name "Net-(A10A-P$2)") (class "Default")
      (node (ref "A10") (pin "A1") (pinfunction "P$2_A1") (pintype "bidirectional"))
      (node (ref "A8") (pin "A1") (pinfunction "P$2_A1") (pintype "bidirectional"))
    )
    (net (code "97") (name "Net-(A10AA-P$2)") (class "Default")
      (node (ref "A10") (pin "R1") (pinfunction "P$2_R1") (pintype "bidirectional"))
      (node (ref "A8") (pin "R1") (pinfunction "P$2_R1") (pintype "bidirectional"))
    )
    (net (code "98") (name "Net-(A10AB-P$2)") (class "Default")
      (node (ref "A10") (pin "R2") (pinfunction "P$2_R2") (pintype "bidirectional"))
      (node (ref "A8") (pin "R2") (pinfunction "P$2_R2") (pintype "bidirectional"))
    )
    (net (code "99") (name "Net-(A10AC-P$2)") (class "Default")
      (node (ref "A10") (pin "S1") (pinfunction "P$2_S1") (pintype "bidirectional"))
      (node (ref "A8") (pin "S1") (pinfunction "P$2_S1") (pintype "bidirectional"))
    )
    (net (code "100") (name "Net-(A10AD-P$2)") (class "Default")
      (node (ref "A10") (pin "S2") (pinfunction "P$2_S2") (pintype "bidirectional"))
      (node (ref "A8") (pin "S2") (pinfunction "P$2_S2") (pintype "bidirectional"))
    )
    (net (code "101") (name "Net-(A10AE-P$2)") (class "Default")
      (node (ref "A10") (pin "T1") (pinfunction "P$2_T1") (pintype "bidirectional"))
      (node (ref "A8") (pin "T1") (pinfunction "P$2_T1") (pintype "bidirectional"))
    )
    (net (code "102") (name "Net-(A10AF-P$2)") (class "Default")
      (node (ref "A10") (pin "T2") (pinfunction "P$2_T2") (pintype "bidirectional"))
      (node (ref "A8") (pin "T2") (pinfunction "P$2_T2") (pintype "bidirectional"))
    )
    (net (code "103") (name "Net-(A10AG-P$2)") (class "Default")
      (node (ref "A10") (pin "U1") (pinfunction "P$2_U1") (pintype "bidirectional"))
      (node (ref "A8") (pin "U1") (pinfunction "P$2_U1") (pintype "bidirectional"))
    )
    (net (code "104") (name "Net-(A10AH-P$2)") (class "Default")
      (node (ref "A10") (pin "U2") (pinfunction "P$2_U2") (pintype "bidirectional"))
      (node (ref "A8") (pin "U2") (pinfunction "P$2_U2") (pintype "bidirectional"))
    )
    (net (code "105") (name "Net-(A10AI-P$2)") (class "Default")
      (node (ref "A10") (pin "V1") (pinfunction "P$2_V1") (pintype "bidirectional"))
      (node (ref "A8") (pin "V1") (pinfunction "P$2_V1") (pintype "bidirectional"))
    )
    (net (code "106") (name "Net-(A10AJ-P$2)") (class "Default")
      (node (ref "A10") (pin "V2") (pinfunction "P$2_V2") (pintype "bidirectional"))
      (node (ref "A8") (pin "V2") (pinfunction "P$2_V2") (pintype "bidirectional"))
    )
    (net (code "107") (name "Net-(A10B-P$2)") (class "Default")
      (node (ref "A10") (pin "A2") (pinfunction "P$2_A2") (pintype "bidirectional"))
      (node (ref "A8") (pin "A2") (pinfunction "P$2_A2") (pintype "bidirectional"))
    )
    (net (code "108") (name "Net-(A10C-P$2)") (class "Default")
      (node (ref "A10") (pin "B1") (pinfunction "P$2_B1") (pintype "bidirectional"))
      (node (ref "A8") (pin "B1") (pinfunction "P$2_B1") (pintype "bidirectional"))
    )
    (net (code "109") (name "Net-(A10D-P$2)") (class "Default")
      (node (ref "A10") (pin "B2") (pinfunction "P$2_B2") (pintype "bidirectional"))
      (node (ref "A8") (pin "B2") (pinfunction "P$2_B2") (pintype "bidirectional"))
    )
    (net (code "110") (name "Net-(A10E-P$2)") (class "Default")
      (node (ref "A10") (pin "C1") (pinfunction "P$2_C1") (pintype "bidirectional"))
      (node (ref "A8") (pin "C1") (pinfunction "P$2_C1") (pintype "bidirectional"))
    )
    (net (code "111") (name "Net-(A10F-P$2)") (class "Default")
      (node (ref "A10") (pin "C2") (pinfunction "P$2_C2") (pintype "bidirectional"))
      (node (ref "A8") (pin "C2") (pinfunction "P$2_C2") (pintype "bidirectional"))
    )
    (net (code "112") (name "Net-(A10G-P$2)") (class "Default")
      (node (ref "A10") (pin "D1") (pinfunction "P$2_D1") (pintype "bidirectional"))
      (node (ref "A8") (pin "D1") (pinfunction "P$2_D1") (pintype "bidirectional"))
    )
    (net (code "113") (name "Net-(A10H-P$2)") (class "Default")
      (node (ref "A10") (pin "D2") (pinfunction "P$2_D2") (pintype "bidirectional"))
      (node (ref "A8") (pin "D2") (pinfunction "P$2_D2") (pintype "bidirectional"))
    )
    (net (code "114") (name "Net-(A10I-P$2)") (class "Default")
      (node (ref "A10") (pin "E1") (pinfunction "P$2_E1") (pintype "bidirectional"))
      (node (ref "A8") (pin "E1") (pinfunction "P$2_E1") (pintype "bidirectional"))
    )
    (net (code "115") (name "Net-(A10J-P$2)") (class "Default")
      (node (ref "A10") (pin "E2") (pinfunction "P$2_E2") (pintype "bidirectional"))
      (node (ref "A8") (pin "E2") (pinfunction "P$2_E2") (pintype "bidirectional"))
    )
    (net (code "116") (name "Net-(A10K-P$2)") (class "Default")
      (node (ref "A10") (pin "F1") (pinfunction "P$2_F1") (pintype "bidirectional"))
      (node (ref "A8") (pin "F1") (pinfunction "P$2_F1") (pintype "bidirectional"))
    )
    (net (code "117") (name "Net-(A10L-P$2)") (class "Default")
      (node (ref "A10") (pin "F2") (pinfunction "P$2_F2") (pintype "bidirectional"))
      (node (ref "A8") (pin "F2") (pinfunction "P$2_F2") (pintype "bidirectional"))
    )
    (net (code "118") (name "Net-(A10M-P$2)") (class "Default")
      (node (ref "A10") (pin "H1") (pinfunction "P$2_H1") (pintype "bidirectional"))
      (node (ref "A8") (pin "H1") (pinfunction "P$2_H1") (pintype "bidirectional"))
    )
    (net (code "119") (name "Net-(A10N-P$2)") (class "Default")
      (node (ref "A10") (pin "H2") (pinfunction "P$2_H2") (pintype "bidirectional"))
      (node (ref "A8") (pin "H2") (pinfunction "P$2_H2") (pintype "bidirectional"))
    )
    (net (code "120") (name "Net-(A10O-P$2)") (class "Default")
      (node (ref "A10") (pin "J1") (pinfunction "P$2_J1") (pintype "bidirectional"))
      (node (ref "A8") (pin "J1") (pinfunction "P$2_J1") (pintype "bidirectional"))
    )
    (net (code "121") (name "Net-(A10P-P$2)") (class "Default")
      (node (ref "A10") (pin "J2") (pinfunction "P$2_J2") (pintype "bidirectional"))
      (node (ref "A8") (pin "J2") (pinfunction "P$2_J2") (pintype "bidirectional"))
    )
    (net (code "122") (name "Net-(A10Q-P$2)") (class "Default")
      (node (ref "A10") (pin "K1") (pinfunction "P$2_K1") (pintype "bidirectional"))
      (node (ref "A8") (pin "K1") (pinfunction "P$2_K1") (pintype "bidirectional"))
    )
    (net (code "123") (name "Net-(A10R-P$2)") (class "Default")
      (node (ref "A10") (pin "K2") (pinfunction "P$2_K2") (pintype "bidirectional"))
      (node (ref "A8") (pin "K2") (pinfunction "P$2_K2") (pintype "bidirectional"))
    )
    (net (code "124") (name "Net-(A10S-P$2)") (class "Default")
      (node (ref "A10") (pin "L1") (pinfunction "P$2_L1") (pintype "bidirectional"))
      (node (ref "A8") (pin "L1") (pinfunction "P$2_L1") (pintype "bidirectional"))
    )
    (net (code "125") (name "Net-(A10T-P$2)") (class "Default")
      (node (ref "A10") (pin "L2") (pinfunction "P$2_L2") (pintype "bidirectional"))
      (node (ref "A8") (pin "L2") (pinfunction "P$2_L2") (pintype "bidirectional"))
    )
    (net (code "126") (name "Net-(A10U-P$2)") (class "Default")
      (node (ref "A10") (pin "M1") (pinfunction "P$2_M1") (pintype "bidirectional"))
      (node (ref "A8") (pin "M1") (pinfunction "P$2_M1") (pintype "bidirectional"))
    )
    (net (code "127") (name "Net-(A10V-P$2)") (class "Default")
      (node (ref "A10") (pin "M2") (pinfunction "P$2_M2") (pintype "bidirectional"))
      (node (ref "A8") (pin "M2") (pinfunction "P$2_M2") (pintype "bidirectional"))
    )
    (net (code "128") (name "Net-(A10W-P$2)") (class "Default")
      (node (ref "A10") (pin "N1") (pinfunction "P$2_N1") (pintype "bidirectional"))
      (node (ref "A8") (pin "N1") (pinfunction "P$2_N1") (pintype "bidirectional"))
    )
    (net (code "129") (name "Net-(A10X-P$2)") (class "Default")
      (node (ref "A10") (pin "N2") (pinfunction "P$2_N2") (pintype "bidirectional"))
      (node (ref "A8") (pin "N2") (pinfunction "P$2_N2") (pintype "bidirectional"))
    )
    (net (code "130") (name "Net-(A10Y-P$2)") (class "Default")
      (node (ref "A10") (pin "P1") (pinfunction "P$2_P1") (pintype "bidirectional"))
      (node (ref "A8") (pin "P1") (pinfunction "P$2_P1") (pintype "bidirectional"))
    )
    (net (code "131") (name "Net-(A10Z-P$2)") (class "Default")
      (node (ref "A10") (pin "P2") (pinfunction "P$2_P2") (pintype "bidirectional"))
      (node (ref "A8") (pin "P2") (pinfunction "P$2_P2") (pintype "bidirectional"))
    )
    (net (code "132") (name "Net-(A11A-P$2)") (class "Default")
      (node (ref "A11") (pin "A1") (pinfunction "P$2_A1") (pintype "bidirectional"))
      (node (ref "A12") (pin "A1") (pinfunction "P$2_A1") (pintype "bidirectional"))
    )
    (net (code "133") (name "Net-(A11AA-P$2)") (class "Default")
      (node (ref "A11") (pin "R1") (pinfunction "P$2_R1") (pintype "bidirectional"))
      (node (ref "A12") (pin "R1") (pinfunction "P$2_R1") (pintype "bidirectional"))
    )
    (net (code "134") (name "Net-(A11AB-P$2)") (class "Default")
      (node (ref "A11") (pin "R2") (pinfunction "P$2_R2") (pintype "bidirectional"))
      (node (ref "A12") (pin "R2") (pinfunction "P$2_R2") (pintype "bidirectional"))
    )
    (net (code "135") (name "Net-(A11AC-P$2)") (class "Default")
      (node (ref "A11") (pin "S1") (pinfunction "P$2_S1") (pintype "bidirectional"))
      (node (ref "A12") (pin "S1") (pinfunction "P$2_S1") (pintype "bidirectional"))
    )
    (net (code "136") (name "Net-(A11AD-P$2)") (class "Default")
      (node (ref "A11") (pin "S2") (pinfunction "P$2_S2") (pintype "bidirectional"))
      (node (ref "A12") (pin "S2") (pinfunction "P$2_S2") (pintype "bidirectional"))
    )
    (net (code "137") (name "Net-(A11AE-P$2)") (class "Default")
      (node (ref "A11") (pin "T1") (pinfunction "P$2_T1") (pintype "bidirectional"))
      (node (ref "A12") (pin "T1") (pinfunction "P$2_T1") (pintype "bidirectional"))
    )
    (net (code "138") (name "Net-(A11AF-P$2)") (class "Default")
      (node (ref "A11") (pin "T2") (pinfunction "P$2_T2") (pintype "bidirectional"))
      (node (ref "A12") (pin "T2") (pinfunction "P$2_T2") (pintype "bidirectional"))
    )
    (net (code "139") (name "Net-(A11AG-P$2)") (class "Default")
      (node (ref "A11") (pin "U1") (pinfunction "P$2_U1") (pintype "bidirectional"))
      (node (ref "A12") (pin "U1") (pinfunction "P$2_U1") (pintype "bidirectional"))
    )
    (net (code "140") (name "Net-(A11AH-P$2)") (class "Default")
      (node (ref "A11") (pin "U2") (pinfunction "P$2_U2") (pintype "bidirectional"))
      (node (ref "A12") (pin "U2") (pinfunction "P$2_U2") (pintype "bidirectional"))
    )
    (net (code "141") (name "Net-(A11AI-P$2)") (class "Default")
      (node (ref "A11") (pin "V1") (pinfunction "P$2_V1") (pintype "bidirectional"))
      (node (ref "A12") (pin "V1") (pinfunction "P$2_V1") (pintype "bidirectional"))
    )
    (net (code "142") (name "Net-(A11AJ-P$2)") (class "Default")
      (node (ref "A11") (pin "V2") (pinfunction "P$2_V2") (pintype "bidirectional"))
      (node (ref "A12") (pin "V2") (pinfunction "P$2_V2") (pintype "bidirectional"))
    )
    (net (code "143") (name "Net-(A11B-P$2)") (class "Default")
      (node (ref "A11") (pin "A2") (pinfunction "P$2_A2") (pintype "bidirectional"))
      (node (ref "A12") (pin "A2") (pinfunction "P$2_A2") (pintype "bidirectional"))
    )
    (net (code "144") (name "Net-(A11C-P$2)") (class "Default")
      (node (ref "A11") (pin "B1") (pinfunction "P$2_B1") (pintype "bidirectional"))
      (node (ref "A12") (pin "B1") (pinfunction "P$2_B1") (pintype "bidirectional"))
    )
    (net (code "145") (name "Net-(A11D-P$2)") (class "Default")
      (node (ref "A11") (pin "B2") (pinfunction "P$2_B2") (pintype "bidirectional"))
      (node (ref "A12") (pin "B2") (pinfunction "P$2_B2") (pintype "bidirectional"))
    )
    (net (code "146") (name "Net-(A11E-P$2)") (class "Default")
      (node (ref "A11") (pin "C1") (pinfunction "P$2_C1") (pintype "bidirectional"))
      (node (ref "A12") (pin "C1") (pinfunction "P$2_C1") (pintype "bidirectional"))
    )
    (net (code "147") (name "Net-(A11F-P$2)") (class "Default")
      (node (ref "A11") (pin "C2") (pinfunction "P$2_C2") (pintype "bidirectional"))
      (node (ref "A12") (pin "C2") (pinfunction "P$2_C2") (pintype "bidirectional"))
    )
    (net (code "148") (name "Net-(A11G-P$2)") (class "Default")
      (node (ref "A11") (pin "D1") (pinfunction "P$2_D1") (pintype "bidirectional"))
      (node (ref "A12") (pin "D1") (pinfunction "P$2_D1") (pintype "bidirectional"))
    )
    (net (code "149") (name "Net-(A11H-P$2)") (class "Default")
      (node (ref "A11") (pin "D2") (pinfunction "P$2_D2") (pintype "bidirectional"))
      (node (ref "A12") (pin "D2") (pinfunction "P$2_D2") (pintype "bidirectional"))
    )
    (net (code "150") (name "Net-(A11I-P$2)") (class "Default")
      (node (ref "A11") (pin "E1") (pinfunction "P$2_E1") (pintype "bidirectional"))
      (node (ref "A12") (pin "E1") (pinfunction "P$2_E1") (pintype "bidirectional"))
    )
    (net (code "151") (name "Net-(A11J-P$2)") (class "Default")
      (node (ref "A11") (pin "E2") (pinfunction "P$2_E2") (pintype "bidirectional"))
      (node (ref "A12") (pin "E2") (pinfunction "P$2_E2") (pintype "bidirectional"))
    )
    (net (code "152") (name "Net-(A11K-P$2)") (class "Default")
      (node (ref "A11") (pin "F1") (pinfunction "P$2_F1") (pintype "bidirectional"))
      (node (ref "A12") (pin "F1") (pinfunction "P$2_F1") (pintype "bidirectional"))
    )
    (net (code "153") (name "Net-(A11L-P$2)") (class "Default")
      (node (ref "A11") (pin "F2") (pinfunction "P$2_F2") (pintype "bidirectional"))
      (node (ref "A12") (pin "F2") (pinfunction "P$2_F2") (pintype "bidirectional"))
    )
    (net (code "154") (name "Net-(A11M-P$2)") (class "Default")
      (node (ref "A11") (pin "H1") (pinfunction "P$2_H1") (pintype "bidirectional"))
      (node (ref "A12") (pin "H1") (pinfunction "P$2_H1") (pintype "bidirectional"))
    )
    (net (code "155") (name "Net-(A11N-P$2)") (class "Default")
      (node (ref "A11") (pin "H2") (pinfunction "P$2_H2") (pintype "bidirectional"))
      (node (ref "A12") (pin "H2") (pinfunction "P$2_H2") (pintype "bidirectional"))
    )
    (net (code "156") (name "Net-(A11O-P$2)") (class "Default")
      (node (ref "A11") (pin "J1") (pinfunction "P$2_J1") (pintype "bidirectional"))
      (node (ref "A12") (pin "J1") (pinfunction "P$2_J1") (pintype "bidirectional"))
    )
    (net (code "157") (name "Net-(A11P-P$2)") (class "Default")
      (node (ref "A11") (pin "J2") (pinfunction "P$2_J2") (pintype "bidirectional"))
      (node (ref "A12") (pin "J2") (pinfunction "P$2_J2") (pintype "bidirectional"))
    )
    (net (code "158") (name "Net-(A11Q-P$2)") (class "Default")
      (node (ref "A11") (pin "K1") (pinfunction "P$2_K1") (pintype "bidirectional"))
      (node (ref "A12") (pin "K1") (pinfunction "P$2_K1") (pintype "bidirectional"))
    )
    (net (code "159") (name "Net-(A11R-P$2)") (class "Default")
      (node (ref "A11") (pin "K2") (pinfunction "P$2_K2") (pintype "bidirectional"))
      (node (ref "A12") (pin "K2") (pinfunction "P$2_K2") (pintype "bidirectional"))
    )
    (net (code "160") (name "Net-(A11S-P$2)") (class "Default")
      (node (ref "A11") (pin "L1") (pinfunction "P$2_L1") (pintype "bidirectional"))
      (node (ref "A12") (pin "L1") (pinfunction "P$2_L1") (pintype "bidirectional"))
    )
    (net (code "161") (name "Net-(A11T-P$2)") (class "Default")
      (node (ref "A11") (pin "L2") (pinfunction "P$2_L2") (pintype "bidirectional"))
      (node (ref "A12") (pin "L2") (pinfunction "P$2_L2") (pintype "bidirectional"))
    )
    (net (code "162") (name "Net-(A11U-P$2)") (class "Default")
      (node (ref "A11") (pin "M1") (pinfunction "P$2_M1") (pintype "bidirectional"))
      (node (ref "A12") (pin "M1") (pinfunction "P$2_M1") (pintype "bidirectional"))
    )
    (net (code "163") (name "Net-(A11V-P$2)") (class "Default")
      (node (ref "A11") (pin "M2") (pinfunction "P$2_M2") (pintype "bidirectional"))
      (node (ref "A12") (pin "M2") (pinfunction "P$2_M2") (pintype "bidirectional"))
    )
    (net (code "164") (name "Net-(A11W-P$2)") (class "Default")
      (node (ref "A11") (pin "N1") (pinfunction "P$2_N1") (pintype "bidirectional"))
      (node (ref "A12") (pin "N1") (pinfunction "P$2_N1") (pintype "bidirectional"))
    )
    (net (code "165") (name "Net-(A11X-P$2)") (class "Default")
      (node (ref "A11") (pin "N2") (pinfunction "P$2_N2") (pintype "bidirectional"))
      (node (ref "A12") (pin "N2") (pinfunction "P$2_N2") (pintype "bidirectional"))
    )
    (net (code "166") (name "Net-(A11Y-P$2)") (class "Default")
      (node (ref "A11") (pin "P1") (pinfunction "P$2_P1") (pintype "bidirectional"))
      (node (ref "A12") (pin "P1") (pinfunction "P$2_P1") (pintype "bidirectional"))
    )
    (net (code "167") (name "Net-(A11Z-P$2)") (class "Default")
      (node (ref "A11") (pin "P2") (pinfunction "P$2_P2") (pintype "bidirectional"))
      (node (ref "A12") (pin "P2") (pinfunction "P$2_P2") (pintype "bidirectional"))
    )
    (net (code "168") (name "Net-(IC1A-I)") (class "Default")
      (node (ref "IC1") (pin "2") (pinfunction "I_2") (pintype "input"))
      (node (ref "OUT1-2") (pin "2") (pinfunction "2_2") (pintype "passive"))
    )
    (net (code "169") (name "Net-(IC1A-OE)") (class "Default")
      (node (ref "IC1") (pin "1") (pinfunction "OE_1") (pintype "input"))
      (node (ref "OUT1-2") (pin "1") (pinfunction "1_1") (pintype "passive"))
    )
    (net (code "170") (name "Net-(IC1B-I)") (class "Default")
      (node (ref "IC1") (pin "5") (pinfunction "I_5") (pintype "input"))
      (node (ref "OUT1-2") (pin "4") (pinfunction "4_4") (pintype "passive"))
    )
    (net (code "171") (name "Net-(IC1B-OE)") (class "Default")
      (node (ref "IC1") (pin "4") (pinfunction "OE_4") (pintype "input"))
      (node (ref "OUT1-2") (pin "3") (pinfunction "3_3") (pintype "passive"))
    )
    (net (code "172") (name "Net-(IC1C-I)") (class "Default")
      (node (ref "IC1") (pin "9") (pinfunction "I_9") (pintype "input"))
      (node (ref "OUT1-2") (pin "6") (pinfunction "6_6") (pintype "passive"))
    )
    (net (code "173") (name "Net-(IC1C-OE)") (class "Default")
      (node (ref "IC1") (pin "10") (pinfunction "OE_10") (pintype "input"))
      (node (ref "OUT1-2") (pin "5") (pinfunction "5_5") (pintype "passive"))
    )
    (net (code "174") (name "Net-(IC1D-I)") (class "Default")
      (node (ref "IC1") (pin "12") (pinfunction "I_12") (pintype "input"))
      (node (ref "OUT1-2") (pin "8") (pinfunction "8_8") (pintype "passive"))
    )
    (net (code "175") (name "Net-(IC1D-OE)") (class "Default")
      (node (ref "IC1") (pin "13") (pinfunction "OE_13") (pintype "input"))
      (node (ref "OUT1-2") (pin "7") (pinfunction "7_7") (pintype "passive"))
    )
    (net (code "176") (name "Net-(IC2A-I)") (class "Default")
      (node (ref "IC2") (pin "2") (pinfunction "I_2") (pintype "input"))
      (node (ref "OUT1-2") (pin "10") (pinfunction "10_10") (pintype "passive"))
    )
    (net (code "177") (name "Net-(IC2A-OE)") (class "Default")
      (node (ref "IC2") (pin "1") (pinfunction "OE_1") (pintype "input"))
      (node (ref "OUT1-2") (pin "9") (pinfunction "9_9") (pintype "passive"))
    )
    (net (code "178") (name "Net-(IC2B-I)") (class "Default")
      (node (ref "IC2") (pin "5") (pinfunction "I_5") (pintype "input"))
      (node (ref "OUT1-2") (pin "12") (pinfunction "12_12") (pintype "passive"))
    )
    (net (code "179") (name "Net-(IC2B-OE)") (class "Default")
      (node (ref "IC2") (pin "4") (pinfunction "OE_4") (pintype "input"))
      (node (ref "OUT1-2") (pin "11") (pinfunction "11_11") (pintype "passive"))
    )
    (net (code "180") (name "Net-(IC2C-I)") (class "Default")
      (node (ref "IC2") (pin "9") (pinfunction "I_9") (pintype "input"))
      (node (ref "OUT1-2") (pin "14") (pinfunction "14_14") (pintype "passive"))
    )
    (net (code "181") (name "Net-(IC2C-OE)") (class "Default")
      (node (ref "IC2") (pin "10") (pinfunction "OE_10") (pintype "input"))
      (node (ref "OUT1-2") (pin "13") (pinfunction "13_13") (pintype "passive"))
    )
    (net (code "182") (name "Net-(IC2D-I)") (class "Default")
      (node (ref "IC2") (pin "12") (pinfunction "I_12") (pintype "input"))
      (node (ref "OUT1-2") (pin "16") (pinfunction "16_16") (pintype "passive"))
    )
    (net (code "183") (name "Net-(IC2D-OE)") (class "Default")
      (node (ref "IC2") (pin "13") (pinfunction "OE_13") (pintype "input"))
      (node (ref "OUT1-2") (pin "15") (pinfunction "15_15") (pintype "passive"))
    )
    (net (code "184") (name "Net-(IC3A-I)") (class "Default")
      (node (ref "IC3") (pin "2") (pinfunction "I_2") (pintype "input"))
      (node (ref "OUT5-6") (pin "2") (pinfunction "2_2") (pintype "passive"))
    )
    (net (code "185") (name "Net-(IC3A-OE)") (class "Default")
      (node (ref "IC3") (pin "1") (pinfunction "OE_1") (pintype "input"))
      (node (ref "OUT5-6") (pin "1") (pinfunction "1_1") (pintype "passive"))
    )
    (net (code "186") (name "Net-(IC3B-I)") (class "Default")
      (node (ref "IC3") (pin "5") (pinfunction "I_5") (pintype "input"))
      (node (ref "OUT5-6") (pin "4") (pinfunction "4_4") (pintype "passive"))
    )
    (net (code "187") (name "Net-(IC3B-OE)") (class "Default")
      (node (ref "IC3") (pin "4") (pinfunction "OE_4") (pintype "input"))
      (node (ref "OUT5-6") (pin "3") (pinfunction "3_3") (pintype "passive"))
    )
    (net (code "188") (name "Net-(IC3C-I)") (class "Default")
      (node (ref "IC3") (pin "9") (pinfunction "I_9") (pintype "input"))
      (node (ref "OUT5-6") (pin "6") (pinfunction "6_6") (pintype "passive"))
    )
    (net (code "189") (name "Net-(IC3C-OE)") (class "Default")
      (node (ref "IC3") (pin "10") (pinfunction "OE_10") (pintype "input"))
      (node (ref "OUT5-6") (pin "5") (pinfunction "5_5") (pintype "passive"))
    )
    (net (code "190") (name "Net-(IC3D-I)") (class "Default")
      (node (ref "IC3") (pin "12") (pinfunction "I_12") (pintype "input"))
      (node (ref "OUT5-6") (pin "8") (pinfunction "8_8") (pintype "passive"))
    )
    (net (code "191") (name "Net-(IC3D-OE)") (class "Default")
      (node (ref "IC3") (pin "13") (pinfunction "OE_13") (pintype "input"))
      (node (ref "OUT5-6") (pin "7") (pinfunction "7_7") (pintype "passive"))
    )
    (net (code "192") (name "Net-(IC4A-I)") (class "Default")
      (node (ref "IC4") (pin "2") (pinfunction "I_2") (pintype "input"))
      (node (ref "OUT5-6") (pin "10") (pinfunction "10_10") (pintype "passive"))
    )
    (net (code "193") (name "Net-(IC4A-OE)") (class "Default")
      (node (ref "IC4") (pin "1") (pinfunction "OE_1") (pintype "input"))
      (node (ref "OUT5-6") (pin "9") (pinfunction "9_9") (pintype "passive"))
    )
    (net (code "194") (name "Net-(IC4B-I)") (class "Default")
      (node (ref "IC4") (pin "5") (pinfunction "I_5") (pintype "input"))
      (node (ref "OUT5-6") (pin "12") (pinfunction "12_12") (pintype "passive"))
    )
    (net (code "195") (name "Net-(IC4B-OE)") (class "Default")
      (node (ref "IC4") (pin "4") (pinfunction "OE_4") (pintype "input"))
      (node (ref "OUT5-6") (pin "11") (pinfunction "11_11") (pintype "passive"))
    )
    (net (code "196") (name "Net-(IC4C-I)") (class "Default")
      (node (ref "IC4") (pin "9") (pinfunction "I_9") (pintype "input"))
      (node (ref "OUT5-6") (pin "14") (pinfunction "14_14") (pintype "passive"))
    )
    (net (code "197") (name "Net-(IC4C-OE)") (class "Default")
      (node (ref "IC4") (pin "10") (pinfunction "OE_10") (pintype "input"))
      (node (ref "OUT5-6") (pin "13") (pinfunction "13_13") (pintype "passive"))
    )
    (net (code "198") (name "Net-(IC4D-I)") (class "Default")
      (node (ref "IC4") (pin "12") (pinfunction "I_12") (pintype "input"))
      (node (ref "OUT5-6") (pin "16") (pinfunction "16_16") (pintype "passive"))
    )
    (net (code "199") (name "Net-(IC4D-OE)") (class "Default")
      (node (ref "IC4") (pin "13") (pinfunction "OE_13") (pintype "input"))
      (node (ref "OUT5-6") (pin "15") (pinfunction "15_15") (pintype "passive"))
    )
    (net (code "200") (name "Net-(IC5A-I)") (class "Default")
      (node (ref "IC5") (pin "2") (pinfunction "I_2") (pintype "input"))
      (node (ref "OUT3-4") (pin "2") (pinfunction "2_2") (pintype "passive"))
    )
    (net (code "201") (name "Net-(IC5A-OE)") (class "Default")
      (node (ref "IC5") (pin "1") (pinfunction "OE_1") (pintype "input"))
      (node (ref "OUT3-4") (pin "1") (pinfunction "1_1") (pintype "passive"))
    )
    (net (code "202") (name "Net-(IC5B-I)") (class "Default")
      (node (ref "IC5") (pin "5") (pinfunction "I_5") (pintype "input"))
      (node (ref "OUT3-4") (pin "4") (pinfunction "4_4") (pintype "passive"))
    )
    (net (code "203") (name "Net-(IC5B-OE)") (class "Default")
      (node (ref "IC5") (pin "4") (pinfunction "OE_4") (pintype "input"))
      (node (ref "OUT3-4") (pin "3") (pinfunction "3_3") (pintype "passive"))
    )
    (net (code "204") (name "Net-(IC5C-I)") (class "Default")
      (node (ref "IC5") (pin "9") (pinfunction "I_9") (pintype "input"))
      (node (ref "OUT3-4") (pin "6") (pinfunction "6_6") (pintype "passive"))
    )
    (net (code "205") (name "Net-(IC5C-OE)") (class "Default")
      (node (ref "IC5") (pin "10") (pinfunction "OE_10") (pintype "input"))
      (node (ref "OUT3-4") (pin "5") (pinfunction "5_5") (pintype "passive"))
    )
    (net (code "206") (name "Net-(IC5D-I)") (class "Default")
      (node (ref "IC5") (pin "12") (pinfunction "I_12") (pintype "input"))
      (node (ref "OUT3-4") (pin "8") (pinfunction "8_8") (pintype "passive"))
    )
    (net (code "207") (name "Net-(IC5D-OE)") (class "Default")
      (node (ref "IC5") (pin "13") (pinfunction "OE_13") (pintype "input"))
      (node (ref "OUT3-4") (pin "7") (pinfunction "7_7") (pintype "passive"))
    )
    (net (code "208") (name "Net-(IC6A-I)") (class "Default")
      (node (ref "IC6") (pin "2") (pinfunction "I_2") (pintype "input"))
      (node (ref "OUT3-4") (pin "10") (pinfunction "10_10") (pintype "passive"))
    )
    (net (code "209") (name "Net-(IC6A-OE)") (class "Default")
      (node (ref "IC6") (pin "1") (pinfunction "OE_1") (pintype "input"))
      (node (ref "OUT3-4") (pin "9") (pinfunction "9_9") (pintype "passive"))
    )
    (net (code "210") (name "Net-(IC6B-I)") (class "Default")
      (node (ref "IC6") (pin "5") (pinfunction "I_5") (pintype "input"))
      (node (ref "OUT3-4") (pin "12") (pinfunction "12_12") (pintype "passive"))
    )
    (net (code "211") (name "Net-(IC6B-OE)") (class "Default")
      (node (ref "IC6") (pin "4") (pinfunction "OE_4") (pintype "input"))
      (node (ref "OUT3-4") (pin "11") (pinfunction "11_11") (pintype "passive"))
    )
    (net (code "212") (name "Net-(IC6C-I)") (class "Default")
      (node (ref "IC6") (pin "9") (pinfunction "I_9") (pintype "input"))
      (node (ref "OUT3-4") (pin "14") (pinfunction "14_14") (pintype "passive"))
    )
    (net (code "213") (name "Net-(IC6C-OE)") (class "Default")
      (node (ref "IC6") (pin "10") (pinfunction "OE_10") (pintype "input"))
      (node (ref "OUT3-4") (pin "13") (pinfunction "13_13") (pintype "passive"))
    )
    (net (code "214") (name "Net-(IC6D-I)") (class "Default")
      (node (ref "IC6") (pin "12") (pinfunction "I_12") (pintype "input"))
      (node (ref "OUT3-4") (pin "16") (pinfunction "16_16") (pintype "passive"))
    )
    (net (code "215") (name "Net-(IC6D-OE)") (class "Default")
      (node (ref "IC6") (pin "13") (pinfunction "OE_13") (pintype "input"))
      (node (ref "OUT3-4") (pin "15") (pinfunction "15_15") (pintype "passive"))
    )
    (net (code "216") (name "Net-(IC7A-I)") (class "Default")
      (node (ref "IC7") (pin "2") (pinfunction "I_2") (pintype "input"))
      (node (ref "OUT7-8") (pin "2") (pinfunction "2_2") (pintype "passive"))
    )
    (net (code "217") (name "Net-(IC7A-OE)") (class "Default")
      (node (ref "IC7") (pin "1") (pinfunction "OE_1") (pintype "input"))
      (node (ref "OUT7-8") (pin "1") (pinfunction "1_1") (pintype "passive"))
    )
    (net (code "218") (name "Net-(IC7B-I)") (class "Default")
      (node (ref "IC7") (pin "5") (pinfunction "I_5") (pintype "input"))
      (node (ref "OUT7-8") (pin "4") (pinfunction "4_4") (pintype "passive"))
    )
    (net (code "219") (name "Net-(IC7B-OE)") (class "Default")
      (node (ref "IC7") (pin "4") (pinfunction "OE_4") (pintype "input"))
      (node (ref "OUT7-8") (pin "3") (pinfunction "3_3") (pintype "passive"))
    )
    (net (code "220") (name "Net-(IC7C-I)") (class "Default")
      (node (ref "IC7") (pin "9") (pinfunction "I_9") (pintype "input"))
      (node (ref "OUT7-8") (pin "6") (pinfunction "6_6") (pintype "passive"))
    )
    (net (code "221") (name "Net-(IC7C-OE)") (class "Default")
      (node (ref "IC7") (pin "10") (pinfunction "OE_10") (pintype "input"))
      (node (ref "OUT7-8") (pin "5") (pinfunction "5_5") (pintype "passive"))
    )
    (net (code "222") (name "Net-(IC7D-I)") (class "Default")
      (node (ref "IC7") (pin "12") (pinfunction "I_12") (pintype "input"))
      (node (ref "OUT7-8") (pin "8") (pinfunction "8_8") (pintype "passive"))
    )
    (net (code "223") (name "Net-(IC7D-OE)") (class "Default")
      (node (ref "IC7") (pin "13") (pinfunction "OE_13") (pintype "input"))
      (node (ref "OUT7-8") (pin "7") (pinfunction "7_7") (pintype "passive"))
    )
    (net (code "224") (name "Net-(IC8A-I)") (class "Default")
      (node (ref "IC8") (pin "2") (pinfunction "I_2") (pintype "input"))
      (node (ref "OUT7-8") (pin "10") (pinfunction "10_10") (pintype "passive"))
    )
    (net (code "225") (name "Net-(IC8A-OE)") (class "Default")
      (node (ref "IC8") (pin "1") (pinfunction "OE_1") (pintype "input"))
      (node (ref "OUT7-8") (pin "9") (pinfunction "9_9") (pintype "passive"))
    )
    (net (code "226") (name "Net-(IC8B-I)") (class "Default")
      (node (ref "IC8") (pin "5") (pinfunction "I_5") (pintype "input"))
      (node (ref "OUT7-8") (pin "12") (pinfunction "12_12") (pintype "passive"))
    )
    (net (code "227") (name "Net-(IC8B-OE)") (class "Default")
      (node (ref "IC8") (pin "4") (pinfunction "OE_4") (pintype "input"))
      (node (ref "OUT7-8") (pin "11") (pinfunction "11_11") (pintype "passive"))
    )
    (net (code "228") (name "Net-(IC8C-I)") (class "Default")
      (node (ref "IC8") (pin "9") (pinfunction "I_9") (pintype "input"))
      (node (ref "OUT7-8") (pin "14") (pinfunction "14_14") (pintype "passive"))
    )
    (net (code "229") (name "Net-(IC8C-OE)") (class "Default")
      (node (ref "IC8") (pin "10") (pinfunction "OE_10") (pintype "input"))
      (node (ref "OUT7-8") (pin "13") (pinfunction "13_13") (pintype "passive"))
    )
    (net (code "230") (name "Net-(IC8D-I)") (class "Default")
      (node (ref "IC8") (pin "12") (pinfunction "I_12") (pintype "input"))
      (node (ref "OUT7-8") (pin "16") (pinfunction "16_16") (pintype "passive"))
    )
    (net (code "231") (name "Net-(IC8D-OE)") (class "Default")
      (node (ref "IC8") (pin "13") (pinfunction "OE_13") (pintype "input"))
      (node (ref "OUT7-8") (pin "15") (pinfunction "15_15") (pintype "passive"))
    )
    (net (code "232") (name "P1") (class "Default")
      (node (ref "IC6") (pin "3") (pinfunction "O_3") (pintype "tri_state"))
      (node (ref "IN1-2") (pin "10") (pinfunction "10_10") (pintype "passive"))
      (node (ref "SV1") (pin "30") (pinfunction "30_30") (pintype "passive"))
    )
    (net (code "233") (name "P2") (class "Default")
      (node (ref "IC7") (pin "8") (pinfunction "O_8") (pintype "tri_state"))
      (node (ref "IN3-4") (pin "13") (pinfunction "13_13") (pintype "passive"))
      (node (ref "SV2") (pin "24") (pinfunction "24_24") (pintype "passive"))
    )
    (net (code "234") (name "R1") (class "Default")
      (node (ref "IC6") (pin "6") (pinfunction "O_6") (pintype "tri_state"))
      (node (ref "IN1-2") (pin "12") (pinfunction "12_12") (pintype "passive"))
      (node (ref "SV1") (pin "26") (pinfunction "26_26") (pintype "passive"))
    )
    (net (code "235") (name "R2") (class "Default")
      (node (ref "IC7") (pin "11") (pinfunction "O_11") (pintype "tri_state"))
      (node (ref "IN3-4") (pin "15") (pinfunction "15_15") (pintype "passive"))
      (node (ref "SV2") (pin "26") (pinfunction "26_26") (pintype "passive"))
    )
    (net (code "236") (name "S1") (class "Default")
      (node (ref "IC6") (pin "8") (pinfunction "O_8") (pintype "tri_state"))
      (node (ref "IN1-2") (pin "14") (pinfunction "14_14") (pintype "passive"))
      (node (ref "SV1") (pin "32") (pinfunction "32_32") (pintype "passive"))
    )
    (net (code "237") (name "S2") (class "Default")
      (node (ref "IC8") (pin "3") (pinfunction "O_3") (pintype "tri_state"))
      (node (ref "IN3-4") (pin "10") (pinfunction "10_10") (pintype "passive"))
      (node (ref "SV2") (pin "28") (pinfunction "28_28") (pintype "passive"))
    )
    (net (code "238") (name "T1") (class "Default")
      (node (ref "SV1") (pin "34") (pinfunction "34_34") (pintype "passive"))
      (node (ref "T1GND") (pin "2") (pinfunction "2_2") (pintype "passive"))
    )
    (net (code "239") (name "T2") (class "Default")
      (node (ref "IC8") (pin "6") (pinfunction "O_6") (pintype "tri_state"))
      (node (ref "IN3-4") (pin "12") (pinfunction "12_12") (pintype "passive"))
      (node (ref "SV2") (pin "30") (pinfunction "30_30") (pintype "passive"))
    )
    (net (code "240") (name "U1") (class "Default")
      (node (ref "IC6") (pin "11") (pinfunction "O_11") (pintype "tri_state"))
      (node (ref "IN1-2") (pin "16") (pinfunction "16_16") (pintype "passive"))
      (node (ref "SV1") (pin "4") (pinfunction "4_4") (pintype "passive"))
    )
    (net (code "241") (name "U2") (class "Default")
      (node (ref "IC8") (pin "8") (pinfunction "O_8") (pintype "tri_state"))
      (node (ref "IN3-4") (pin "14") (pinfunction "14_14") (pintype "passive"))
      (node (ref "SV2") (pin "34") (pinfunction "34_34") (pintype "passive"))
    )
    (net (code "242") (name "V1") (class "Default")
      (node (ref "IC3") (pin "3") (pinfunction "O_3") (pintype "tri_state"))
      (node (ref "IN3-4") (pin "1") (pinfunction "1_1") (pintype "passive"))
      (node (ref "SV1") (pin "2") (pinfunction "2_2") (pintype "passive"))
    )
    (net (code "243") (name "V2") (class "Default")
      (node (ref "IC8") (pin "11") (pinfunction "O_11") (pintype "tri_state"))
      (node (ref "IN3-4") (pin "16") (pinfunction "16_16") (pintype "passive"))
      (node (ref "SV2") (pin "32") (pinfunction "32_32") (pintype "passive"))
    )
    (net (code "244") (name "VCC") (class "Default")
      (node (ref "BYP1") (pin "1") (pinfunction "1_1") (pintype "passive"))
      (node (ref "BYP10") (pin "1") (pinfunction "1_1") (pintype "passive"))
      (node (ref "BYP2") (pin "1") (pinfunction "1_1") (pintype "passive"))
      (node (ref "BYP3") (pin "1") (pinfunction "1_1") (pintype "passive"))
      (node (ref "BYP4") (pin "1") (pinfunction "1_1") (pintype "passive"))
      (node (ref "BYP5") (pin "1") (pinfunction "1_1") (pintype "passive"))
      (node (ref "BYP6") (pin "1") (pinfunction "1_1") (pintype "passive"))
      (node (ref "BYP7") (pin "1") (pinfunction "1_1") (pintype "passive"))
      (node (ref "BYP8") (pin "1") (pinfunction "1_1") (pintype "passive"))
      (node (ref "CORE-IO") (pin "12") (pinfunction "12_12") (pintype "passive"))
      (node (ref "CORE-IO") (pin "9") (pinfunction "9_9") (pintype "passive"))
      (node (ref "JP2") (pin "2") (pinfunction "2_2") (pintype "passive"))
      (node (ref "SV2") (pin "2") (pinfunction "2_2") (pintype "passive"))
    )
    (net (code "245") (name "unconnected-(CORE-IO-Pad1)") (class "Default")
      (node (ref "CORE-IO") (pin "1") (pinfunction "1_1") (pintype "passive"))
    )
    (net (code "246") (name "unconnected-(CORE-IO-Pad2)") (class "Default")
      (node (ref "CORE-IO") (pin "2") (pinfunction "2_2") (pintype "passive"))
    )
    (net (code "247") (name "unconnected-(CORE-IO-Pad3)") (class "Default")
      (node (ref "CORE-IO") (pin "3") (pinfunction "3_3") (pintype "passive"))
    )
    (net (code "248") (name "unconnected-(CORE-IO-Pad4)") (class "Default")
      (node (ref "CORE-IO") (pin "4") (pinfunction "4_4") (pintype "passive"))
    )
    (net (code "249") (name "unconnected-(CORE-IO-Pad5)") (class "Default")
      (node (ref "CORE-IO") (pin "5") (pinfunction "5_5") (pintype "passive"))
    )
    (net (code "250") (name "unconnected-(CORE-IO-Pad6)") (class "Default")
      (node (ref "CORE-IO") (pin "6") (pinfunction "6_6") (pintype "passive"))
    )
    (net (code "251") (name "unconnected-(CORE-IO-Pad7)") (class "Default")
      (node (ref "CORE-IO") (pin "7") (pinfunction "7_7") (pintype "passive"))
    )
    (net (code "252") (name "unconnected-(CORE-IO-Pad8)") (class "Default")
      (node (ref "CORE-IO") (pin "8") (pinfunction "8_8") (pintype "passive"))
    )
    (net (code "253") (name "unconnected-(CORE-IO-Pad13)") (class "Default")
      (node (ref "CORE-IO") (pin "13") (pinfunction "13_13") (pintype "passive"))
    )
    (net (code "254") (name "unconnected-(CORE-IO-Pad14)") (class "Default")
      (node (ref "CORE-IO") (pin "14") (pinfunction "14_14") (pintype "passive"))
    )
    (net (code "255") (name "unconnected-(CORE-IO-Pad15)") (class "Default")
      (node (ref "CORE-IO") (pin "15") (pinfunction "15_15") (pintype "passive"))
    )
    (net (code "256") (name "unconnected-(CORE-IO-Pad16)") (class "Default")
      (node (ref "CORE-IO") (pin "16") (pinfunction "16_16") (pintype "passive"))
    )
    (net (code "257") (name "unconnected-(CORE-IO-Pad17)") (class "Default")
      (node (ref "CORE-IO") (pin "17") (pinfunction "17_17") (pintype "passive"))
    )
    (net (code "258") (name "unconnected-(CORE-IO-Pad18)") (class "Default")
      (node (ref "CORE-IO") (pin "18") (pinfunction "18_18") (pintype "passive"))
    )
    (net (code "259") (name "unconnected-(CORE-IO-Pad19)") (class "Default")
      (node (ref "CORE-IO") (pin "19") (pinfunction "19_19") (pintype "passive"))
    )
    (net (code "260") (name "unconnected-(CORE-IO-Pad20)") (class "Default")
      (node (ref "CORE-IO") (pin "20") (pinfunction "20_20") (pintype "passive"))
    )
    (net (code "261") (name "unconnected-(IN5-6-Pad1)") (class "Default")
      (node (ref "IN5-6") (pin "1") (pinfunction "1_1") (pintype "passive"))
    )
    (net (code "262") (name "unconnected-(IN5-6-Pad2)") (class "Default")
      (node (ref "IN5-6") (pin "2") (pinfunction "2_2") (pintype "passive"))
    )
    (net (code "263") (name "unconnected-(IN5-6-Pad3)") (class "Default")
      (node (ref "IN5-6") (pin "3") (pinfunction "3_3") (pintype "passive"))
    )
    (net (code "264") (name "unconnected-(IN5-6-Pad4)") (class "Default")
      (node (ref "IN5-6") (pin "4") (pinfunction "4_4") (pintype "passive"))
    )
    (net (code "265") (name "unconnected-(IN5-6-Pad5)") (class "Default")
      (node (ref "IN5-6") (pin "5") (pinfunction "5_5") (pintype "passive"))
    )
    (net (code "266") (name "unconnected-(IN5-6-Pad6)") (class "Default")
      (node (ref "IN5-6") (pin "6") (pinfunction "6_6") (pintype "passive"))
    )
    (net (code "267") (name "unconnected-(IN5-6-Pad7)") (class "Default")
      (node (ref "IN5-6") (pin "7") (pinfunction "7_7") (pintype "passive"))
    )
    (net (code "268") (name "unconnected-(IN5-6-Pad8)") (class "Default")
      (node (ref "IN5-6") (pin "8") (pinfunction "8_8") (pintype "passive"))
    )
    (net (code "269") (name "unconnected-(IN5-6-Pad9)") (class "Default")
      (node (ref "IN5-6") (pin "9") (pinfunction "9_9") (pintype "passive"))
    )
    (net (code "270") (name "unconnected-(IN5-6-Pad10)") (class "Default")
      (node (ref "IN5-6") (pin "10") (pinfunction "10_10") (pintype "passive"))
    )
    (net (code "271") (name "unconnected-(IN5-6-Pad11)") (class "Default")
      (node (ref "IN5-6") (pin "11") (pinfunction "11_11") (pintype "passive"))
    )
    (net (code "272") (name "unconnected-(IN5-6-Pad12)") (class "Default")
      (node (ref "IN5-6") (pin "12") (pinfunction "12_12") (pintype "passive"))
    )
    (net (code "273") (name "unconnected-(IN5-6-Pad13)") (class "Default")
      (node (ref "IN5-6") (pin "13") (pinfunction "13_13") (pintype "passive"))
    )
    (net (code "274") (name "unconnected-(IN5-6-Pad14)") (class "Default")
      (node (ref "IN5-6") (pin "14") (pinfunction "14_14") (pintype "passive"))
    )
    (net (code "275") (name "unconnected-(IN5-6-Pad15)") (class "Default")
      (node (ref "IN5-6") (pin "15") (pinfunction "15_15") (pintype "passive"))
    )
    (net (code "276") (name "unconnected-(IN5-6-Pad16)") (class "Default")
      (node (ref "IN5-6") (pin "16") (pinfunction "16_16") (pintype "passive"))
    )
    (net (code "277") (name "unconnected-(IN7-8-Pad1)") (class "Default")
      (node (ref "IN7-8") (pin "1") (pinfunction "1_1") (pintype "passive"))
    )
    (net (code "278") (name "unconnected-(IN7-8-Pad2)") (class "Default")
      (node (ref "IN7-8") (pin "2") (pinfunction "2_2") (pintype "passive"))
    )
    (net (code "279") (name "unconnected-(IN7-8-Pad3)") (class "Default")
      (node (ref "IN7-8") (pin "3") (pinfunction "3_3") (pintype "passive"))
    )
    (net (code "280") (name "unconnected-(IN7-8-Pad4)") (class "Default")
      (node (ref "IN7-8") (pin "4") (pinfunction "4_4") (pintype "passive"))
    )
    (net (code "281") (name "unconnected-(IN7-8-Pad5)") (class "Default")
      (node (ref "IN7-8") (pin "5") (pinfunction "5_5") (pintype "passive"))
    )
    (net (code "282") (name "unconnected-(IN7-8-Pad6)") (class "Default")
      (node (ref "IN7-8") (pin "6") (pinfunction "6_6") (pintype "passive"))
    )
    (net (code "283") (name "unconnected-(IN7-8-Pad7)") (class "Default")
      (node (ref "IN7-8") (pin "7") (pinfunction "7_7") (pintype "passive"))
    )
    (net (code "284") (name "unconnected-(IN7-8-Pad8)") (class "Default")
      (node (ref "IN7-8") (pin "8") (pinfunction "8_8") (pintype "passive"))
    )
    (net (code "285") (name "unconnected-(IN7-8-Pad9)") (class "Default")
      (node (ref "IN7-8") (pin "9") (pinfunction "9_9") (pintype "passive"))
    )
    (net (code "286") (name "unconnected-(IN7-8-Pad10)") (class "Default")
      (node (ref "IN7-8") (pin "10") (pinfunction "10_10") (pintype "passive"))
    )
    (net (code "287") (name "unconnected-(IN7-8-Pad11)") (class "Default")
      (node (ref "IN7-8") (pin "11") (pinfunction "11_11") (pintype "passive"))
    )
    (net (code "288") (name "unconnected-(IN7-8-Pad12)") (class "Default")
      (node (ref "IN7-8") (pin "12") (pinfunction "12_12") (pintype "passive"))
    )
    (net (code "289") (name "unconnected-(IN7-8-Pad13)") (class "Default")
      (node (ref "IN7-8") (pin "13") (pinfunction "13_13") (pintype "passive"))
    )
    (net (code "290") (name "unconnected-(IN7-8-Pad14)") (class "Default")
      (node (ref "IN7-8") (pin "14") (pinfunction "14_14") (pintype "passive"))
    )
    (net (code "291") (name "unconnected-(IN7-8-Pad15)") (class "Default")
      (node (ref "IN7-8") (pin "15") (pinfunction "15_15") (pintype "passive"))
    )
    (net (code "292") (name "unconnected-(IN7-8-Pad16)") (class "Default")
      (node (ref "IN7-8") (pin "16") (pinfunction "16_16") (pintype "passive"))
    )
    (net (code "293") (name "unconnected-(JP1-Pad1)") (class "Default")
      (node (ref "JP1") (pin "1") (pinfunction "1_1") (pintype "passive"))
    )
    (net (code "294") (name "unconnected-(JP1-Pad2)") (class "Default")
      (node (ref "JP1") (pin "2") (pinfunction "2_2") (pintype "passive"))
    )
    (net (code "295") (name "unconnected-(JP1-Pad3)") (class "Default")
      (node (ref "JP1") (pin "3") (pinfunction "3_3") (pintype "passive"))
    )
    (net (code "296") (name "unconnected-(JP1-Pad4)") (class "Default")
      (node (ref "JP1") (pin "4") (pinfunction "4_4") (pintype "passive"))
    )
    (net (code "297") (name "unconnected-(JP1-Pad5)") (class "Default")
      (node (ref "JP1") (pin "5") (pinfunction "5_5") (pintype "passive"))
    )
    (net (code "298") (name "unconnected-(JP1-Pad6)") (class "Default")
      (node (ref "JP1") (pin "6") (pinfunction "6_6") (pintype "passive"))
    )
    (net (code "299") (name "unconnected-(JP1-Pad7)") (class "Default")
      (node (ref "JP1") (pin "7") (pinfunction "7_7") (pintype "passive"))
    )
    (net (code "300") (name "unconnected-(JP1-Pad8)") (class "Default")
      (node (ref "JP1") (pin "8") (pinfunction "8_8") (pintype "passive"))
    )
    (net (code "301") (name "unconnected-(JP1-Pad9)") (class "Default")
      (node (ref "JP1") (pin "9") (pinfunction "9_9") (pintype "passive"))
    )
    (net (code "302") (name "unconnected-(JP1-Pad10)") (class "Default")
      (node (ref "JP1") (pin "10") (pinfunction "10_10") (pintype "passive"))
    )
    (net (code "303") (name "unconnected-(JP1-Pad11)") (class "Default")
      (node (ref "JP1") (pin "11") (pinfunction "11_11") (pintype "passive"))
    )
    (net (code "304") (name "unconnected-(JP1-Pad12)") (class "Default")
      (node (ref "JP1") (pin "12") (pinfunction "12_12") (pintype "passive"))
    )
    (net (code "305") (name "unconnected-(JP1-Pad13)") (class "Default")
      (node (ref "JP1") (pin "13") (pinfunction "13_13") (pintype "passive"))
    )
    (net (code "306") (name "unconnected-(JP1-Pad14)") (class "Default")
      (node (ref "JP1") (pin "14") (pinfunction "14_14") (pintype "passive"))
    )
    (net (code "307") (name "unconnected-(JP1-Pad15)") (class "Default")
      (node (ref "JP1") (pin "15") (pinfunction "15_15") (pintype "passive"))
    )
    (net (code "308") (name "unconnected-(JP1-Pad16)") (class "Default")
      (node (ref "JP1") (pin "16") (pinfunction "16_16") (pintype "passive"))
    )
    (net (code "309") (name "unconnected-(JP1-Pad17)") (class "Default")
      (node (ref "JP1") (pin "17") (pinfunction "17_17") (pintype "passive"))
    )
    (net (code "310") (name "unconnected-(JP1-Pad18)") (class "Default")
      (node (ref "JP1") (pin "18") (pinfunction "18_18") (pintype "passive"))
    )
    (net (code "311") (name "unconnected-(JP3-Pad1)") (class "Default")
      (node (ref "JP3") (pin "1") (pinfunction "1_1") (pintype "passive"))
    )
    (net (code "312") (name "unconnected-(JP3-Pad2)") (class "Default")
      (node (ref "JP3") (pin "2") (pinfunction "2_2") (pintype "passive"))
    )
    (net (code "313") (name "unconnected-(JP3-Pad3)") (class "Default")
      (node (ref "JP3") (pin "3") (pinfunction "3_3") (pintype "passive"))
    )
    (net (code "314") (name "unconnected-(JP3-Pad4)") (class "Default")
      (node (ref "JP3") (pin "4") (pinfunction "4_4") (pintype "passive"))
    )
    (net (code "315") (name "unconnected-(JP3-Pad5)") (class "Default")
      (node (ref "JP3") (pin "5") (pinfunction "5_5") (pintype "passive"))
    )
    (net (code "316") (name "unconnected-(JP3-Pad6)") (class "Default")
      (node (ref "JP3") (pin "6") (pinfunction "6_6") (pintype "passive"))
    )
    (net (code "317") (name "unconnected-(JP3-Pad7)") (class "Default")
      (node (ref "JP3") (pin "7") (pinfunction "7_7") (pintype "passive"))
    )
    (net (code "318") (name "unconnected-(JP3-Pad8)") (class "Default")
      (node (ref "JP3") (pin "8") (pinfunction "8_8") (pintype "passive"))
    )
    (net (code "319") (name "unconnected-(JP3-Pad9)") (class "Default")
      (node (ref "JP3") (pin "9") (pinfunction "9_9") (pintype "passive"))
    )
    (net (code "320") (name "unconnected-(JP3-Pad10)") (class "Default")
      (node (ref "JP3") (pin "10") (pinfunction "10_10") (pintype "passive"))
    )
    (net (code "321") (name "unconnected-(JP3-Pad11)") (class "Default")
      (node (ref "JP3") (pin "11") (pinfunction "11_11") (pintype "passive"))
    )
    (net (code "322") (name "unconnected-(JP3-Pad12)") (class "Default")
      (node (ref "JP3") (pin "12") (pinfunction "12_12") (pintype "passive"))
    )
    (net (code "323") (name "unconnected-(JP3-Pad13)") (class "Default")
      (node (ref "JP3") (pin "13") (pinfunction "13_13") (pintype "passive"))
    )
    (net (code "324") (name "unconnected-(JP3-Pad14)") (class "Default")
      (node (ref "JP3") (pin "14") (pinfunction "14_14") (pintype "passive"))
    )
    (net (code "325") (name "unconnected-(JP3-Pad15)") (class "Default")
      (node (ref "JP3") (pin "15") (pinfunction "15_15") (pintype "passive"))
    )
    (net (code "326") (name "unconnected-(JP3-Pad16)") (class "Default")
      (node (ref "JP3") (pin "16") (pinfunction "16_16") (pintype "passive"))
    )
    (net (code "327") (name "unconnected-(JP3-Pad17)") (class "Default")
      (node (ref "JP3") (pin "17") (pinfunction "17_17") (pintype "passive"))
    )
    (net (code "328") (name "unconnected-(JP3-Pad18)") (class "Default")
      (node (ref "JP3") (pin "18") (pinfunction "18_18") (pintype "passive"))
    )
    (net (code "329") (name "unconnected-(JP4-Pad1)") (class "Default")
      (node (ref "JP4") (pin "1") (pinfunction "1_1") (pintype "passive"))
    )
    (net (code "330") (name "unconnected-(JP4-Pad2)") (class "Default")
      (node (ref "JP4") (pin "2") (pinfunction "2_2") (pintype "passive"))
    )
    (net (code "331") (name "unconnected-(JP4-Pad3)") (class "Default")
      (node (ref "JP4") (pin "3") (pinfunction "3_3") (pintype "passive"))
    )
    (net (code "332") (name "unconnected-(JP4-Pad4)") (class "Default")
      (node (ref "JP4") (pin "4") (pinfunction "4_4") (pintype "passive"))
    )
    (net (code "333") (name "unconnected-(JP4-Pad5)") (class "Default")
      (node (ref "JP4") (pin "5") (pinfunction "5_5") (pintype "passive"))
    )
    (net (code "334") (name "unconnected-(JP4-Pad6)") (class "Default")
      (node (ref "JP4") (pin "6") (pinfunction "6_6") (pintype "passive"))
    )
    (net (code "335") (name "unconnected-(JP4-Pad7)") (class "Default")
      (node (ref "JP4") (pin "7") (pinfunction "7_7") (pintype "passive"))
    )
    (net (code "336") (name "unconnected-(JP4-Pad8)") (class "Default")
      (node (ref "JP4") (pin "8") (pinfunction "8_8") (pintype "passive"))
    )
    (net (code "337") (name "unconnected-(JP4-Pad9)") (class "Default")
      (node (ref "JP4") (pin "9") (pinfunction "9_9") (pintype "passive"))
    )
    (net (code "338") (name "unconnected-(JP4-Pad10)") (class "Default")
      (node (ref "JP4") (pin "10") (pinfunction "10_10") (pintype "passive"))
    )
    (net (code "339") (name "unconnected-(JP4-Pad11)") (class "Default")
      (node (ref "JP4") (pin "11") (pinfunction "11_11") (pintype "passive"))
    )
    (net (code "340") (name "unconnected-(JP4-Pad12)") (class "Default")
      (node (ref "JP4") (pin "12") (pinfunction "12_12") (pintype "passive"))
    )
    (net (code "341") (name "unconnected-(JP4-Pad13)") (class "Default")
      (node (ref "JP4") (pin "13") (pinfunction "13_13") (pintype "passive"))
    )
    (net (code "342") (name "unconnected-(JP4-Pad14)") (class "Default")
      (node (ref "JP4") (pin "14") (pinfunction "14_14") (pintype "passive"))
    )
    (net (code "343") (name "unconnected-(JP4-Pad15)") (class "Default")
      (node (ref "JP4") (pin "15") (pinfunction "15_15") (pintype "passive"))
    )
    (net (code "344") (name "unconnected-(JP4-Pad16)") (class "Default")
      (node (ref "JP4") (pin "16") (pinfunction "16_16") (pintype "passive"))
    )
    (net (code "345") (name "unconnected-(JP4-Pad17)") (class "Default")
      (node (ref "JP4") (pin "17") (pinfunction "17_17") (pintype "passive"))
    )
    (net (code "346") (name "unconnected-(JP4-Pad18)") (class "Default")
      (node (ref "JP4") (pin "18") (pinfunction "18_18") (pintype "passive"))
    )
    (net (code "347") (name "unconnected-(JP5-Pad1)") (class "Default")
      (node (ref "JP5") (pin "1") (pinfunction "1_1") (pintype "passive"))
    )
    (net (code "348") (name "unconnected-(JP5-Pad2)") (class "Default")
      (node (ref "JP5") (pin "2") (pinfunction "2_2") (pintype "passive"))
    )
    (net (code "349") (name "unconnected-(JP5-Pad3)") (class "Default")
      (node (ref "JP5") (pin "3") (pinfunction "3_3") (pintype "passive"))
    )
    (net (code "350") (name "unconnected-(JP5-Pad4)") (class "Default")
      (node (ref "JP5") (pin "4") (pinfunction "4_4") (pintype "passive"))
    )
    (net (code "351") (name "unconnected-(JP5-Pad5)") (class "Default")
      (node (ref "JP5") (pin "5") (pinfunction "5_5") (pintype "passive"))
    )
    (net (code "352") (name "unconnected-(JP5-Pad6)") (class "Default")
      (node (ref "JP5") (pin "6") (pinfunction "6_6") (pintype "passive"))
    )
    (net (code "353") (name "unconnected-(JP5-Pad7)") (class "Default")
      (node (ref "JP5") (pin "7") (pinfunction "7_7") (pintype "passive"))
    )
    (net (code "354") (name "unconnected-(JP5-Pad8)") (class "Default")
      (node (ref "JP5") (pin "8") (pinfunction "8_8") (pintype "passive"))
    )
    (net (code "355") (name "unconnected-(JP5-Pad9)") (class "Default")
      (node (ref "JP5") (pin "9") (pinfunction "9_9") (pintype "passive"))
    )
    (net (code "356") (name "unconnected-(JP5-Pad10)") (class "Default")
      (node (ref "JP5") (pin "10") (pinfunction "10_10") (pintype "passive"))
    )
    (net (code "357") (name "unconnected-(JP5-Pad11)") (class "Default")
      (node (ref "JP5") (pin "11") (pinfunction "11_11") (pintype "passive"))
    )
    (net (code "358") (name "unconnected-(JP5-Pad12)") (class "Default")
      (node (ref "JP5") (pin "12") (pinfunction "12_12") (pintype "passive"))
    )
    (net (code "359") (name "unconnected-(JP5-Pad13)") (class "Default")
      (node (ref "JP5") (pin "13") (pinfunction "13_13") (pintype "passive"))
    )
    (net (code "360") (name "unconnected-(JP5-Pad14)") (class "Default")
      (node (ref "JP5") (pin "14") (pinfunction "14_14") (pintype "passive"))
    )
    (net (code "361") (name "unconnected-(JP5-Pad15)") (class "Default")
      (node (ref "JP5") (pin "15") (pinfunction "15_15") (pintype "passive"))
    )
    (net (code "362") (name "unconnected-(JP5-Pad16)") (class "Default")
      (node (ref "JP5") (pin "16") (pinfunction "16_16") (pintype "passive"))
    )
    (net (code "363") (name "unconnected-(JP5-Pad17)") (class "Default")
      (node (ref "JP5") (pin "17") (pinfunction "17_17") (pintype "passive"))
    )
    (net (code "364") (name "unconnected-(JP5-Pad18)") (class "Default")
      (node (ref "JP5") (pin "18") (pinfunction "18_18") (pintype "passive"))
    )
    (net (code "365") (name "unconnected-(SW1-Pad1)") (class "Default")
      (node (ref "SW1") (pin "1") (pinfunction "1_1") (pintype "passive"))
    )
    (net (code "366") (name "unconnected-(SW1-Pad2)") (class "Default")
      (node (ref "SW1") (pin "2") (pinfunction "2_2") (pintype "passive"))
    )
    (net (code "367") (name "unconnected-(SW1-Pad3)") (class "Default")
      (node (ref "SW1") (pin "3") (pinfunction "3_3") (pintype "passive"))
    )
    (net (code "368") (name "unconnected-(SW1-Pad4)") (class "Default")
      (node (ref "SW1") (pin "4") (pinfunction "4_4") (pintype "passive"))
    )
    (net (code "369") (name "unconnected-(SW1-Pad5)") (class "Default")
      (node (ref "SW1") (pin "5") (pinfunction "5_5") (pintype "passive"))
    )
    (net (code "370") (name "unconnected-(SW1-Pad6)") (class "Default")
      (node (ref "SW1") (pin "6") (pinfunction "6_6") (pintype "passive"))
    )
    (net (code "371") (name "unconnected-(SW1-Pad7)") (class "Default")
      (node (ref "SW1") (pin "7") (pinfunction "7_7") (pintype "passive"))
    )
    (net (code "372") (name "unconnected-(SW1-Pad8)") (class "Default")
      (node (ref "SW1") (pin "8") (pinfunction "8_8") (pintype "passive"))
    )
    (net (code "373") (name "unconnected-(SW1-Pad9)") (class "Default")
      (node (ref "SW1") (pin "9") (pinfunction "9_9") (pintype "passive"))
    )
    (net (code "374") (name "unconnected-(SW1-Pad10)") (class "Default")
      (node (ref "SW1") (pin "10") (pinfunction "10_10") (pintype "passive"))
    )
    (net (code "375") (name "unconnected-(SW1-Pad11)") (class "Default")
      (node (ref "SW1") (pin "11") (pinfunction "11_11") (pintype "passive"))
    )
    (net (code "376") (name "unconnected-(SW1-Pad12)") (class "Default")
      (node (ref "SW1") (pin "12") (pinfunction "12_12") (pintype "passive"))
    )
    (net (code "377") (name "unconnected-(SW1-Pad13)") (class "Default")
      (node (ref "SW1") (pin "13") (pinfunction "13_13") (pintype "passive"))
    )
    (net (code "378") (name "unconnected-(SW1-Pad14)") (class "Default")
      (node (ref "SW1") (pin "14") (pinfunction "14_14") (pintype "passive"))
    )
    (net (code "379") (name "unconnected-(SW1-Pad15)") (class "Default")
      (node (ref "SW1") (pin "15") (pinfunction "15_15") (pintype "passive"))
    )
    (net (code "380") (name "unconnected-(SW1-Pad16)") (class "Default")
      (node (ref "SW1") (pin "16") (pinfunction "16_16") (pintype "passive"))
    )
    (net (code "381") (name "unconnected-(SW2-Pad1)") (class "Default")
      (node (ref "SW2") (pin "1") (pinfunction "1_1") (pintype "passive"))
    )
    (net (code "382") (name "unconnected-(SW2-Pad2)") (class "Default")
      (node (ref "SW2") (pin "2") (pinfunction "2_2") (pintype "passive"))
    )
    (net (code "383") (name "unconnected-(SW2-Pad3)") (class "Default")
      (node (ref "SW2") (pin "3") (pinfunction "3_3") (pintype "passive"))
    )
    (net (code "384") (name "unconnected-(SW2-Pad4)") (class "Default")
      (node (ref "SW2") (pin "4") (pinfunction "4_4") (pintype "passive"))
    )
    (net (code "385") (name "unconnected-(SW2-Pad5)") (class "Default")
      (node (ref "SW2") (pin "5") (pinfunction "5_5") (pintype "passive"))
    )
    (net (code "386") (name "unconnected-(SW2-Pad6)") (class "Default")
      (node (ref "SW2") (pin "6") (pinfunction "6_6") (pintype "passive"))
    )
    (net (code "387") (name "unconnected-(SW2-Pad7)") (class "Default")
      (node (ref "SW2") (pin "7") (pinfunction "7_7") (pintype "passive"))
    )
    (net (code "388") (name "unconnected-(SW2-Pad8)") (class "Default")
      (node (ref "SW2") (pin "8") (pinfunction "8_8") (pintype "passive"))
    )
    (net (code "389") (name "unconnected-(SW2-Pad9)") (class "Default")
      (node (ref "SW2") (pin "9") (pinfunction "9_9") (pintype "passive"))
    )
    (net (code "390") (name "unconnected-(SW2-Pad10)") (class "Default")
      (node (ref "SW2") (pin "10") (pinfunction "10_10") (pintype "passive"))
    )
    (net (code "391") (name "unconnected-(SW2-Pad11)") (class "Default")
      (node (ref "SW2") (pin "11") (pinfunction "11_11") (pintype "passive"))
    )
    (net (code "392") (name "unconnected-(SW2-Pad12)") (class "Default")
      (node (ref "SW2") (pin "12") (pinfunction "12_12") (pintype "passive"))
    )
    (net (code "393") (name "unconnected-(SW2-Pad13)") (class "Default")
      (node (ref "SW2") (pin "13") (pinfunction "13_13") (pintype "passive"))
    )
    (net (code "394") (name "unconnected-(SW2-Pad14)") (class "Default")
      (node (ref "SW2") (pin "14") (pinfunction "14_14") (pintype "passive"))
    )
    (net (code "395") (name "unconnected-(SW2-Pad15)") (class "Default")
      (node (ref "SW2") (pin "15") (pinfunction "15_15") (pintype "passive"))
    )
    (net (code "396") (name "unconnected-(SW2-Pad16)") (class "Default")
      (node (ref "SW2") (pin "16") (pinfunction "16_16") (pintype "passive"))
    )
    (net (code "397") (name "unconnected-(SW3-Pad1)") (class "Default")
      (node (ref "SW3") (pin "1") (pinfunction "1_1") (pintype "passive"))
    )
    (net (code "398") (name "unconnected-(SW3-Pad2)") (class "Default")
      (node (ref "SW3") (pin "2") (pinfunction "2_2") (pintype "passive"))
    )
    (net (code "399") (name "unconnected-(SW3-Pad3)") (class "Default")
      (node (ref "SW3") (pin "3") (pinfunction "3_3") (pintype "passive"))
    )
    (net (code "400") (name "unconnected-(SW3-Pad4)") (class "Default")
      (node (ref "SW3") (pin "4") (pinfunction "4_4") (pintype "passive"))
    )
    (net (code "401") (name "unconnected-(SW3-Pad5)") (class "Default")
      (node (ref "SW3") (pin "5") (pinfunction "5_5") (pintype "passive"))
    )
    (net (code "402") (name "unconnected-(SW3-Pad6)") (class "Default")
      (node (ref "SW3") (pin "6") (pinfunction "6_6") (pintype "passive"))
    )
    (net (code "403") (name "unconnected-(SW3-Pad7)") (class "Default")
      (node (ref "SW3") (pin "7") (pinfunction "7_7") (pintype "passive"))
    )
    (net (code "404") (name "unconnected-(SW3-Pad8)") (class "Default")
      (node (ref "SW3") (pin "8") (pinfunction "8_8") (pintype "passive"))
    )
    (net (code "405") (name "unconnected-(SW3-Pad9)") (class "Default")
      (node (ref "SW3") (pin "9") (pinfunction "9_9") (pintype "passive"))
    )
    (net (code "406") (name "unconnected-(SW3-Pad10)") (class "Default")
      (node (ref "SW3") (pin "10") (pinfunction "10_10") (pintype "passive"))
    )
    (net (code "407") (name "unconnected-(SW3-Pad11)") (class "Default")
      (node (ref "SW3") (pin "11") (pinfunction "11_11") (pintype "passive"))
    )
    (net (code "408") (name "unconnected-(SW3-Pad12)") (class "Default")
      (node (ref "SW3") (pin "12") (pinfunction "12_12") (pintype "passive"))
    )
    (net (code "409") (name "unconnected-(SW3-Pad13)") (class "Default")
      (node (ref "SW3") (pin "13") (pinfunction "13_13") (pintype "passive"))
    )
    (net (code "410") (name "unconnected-(SW3-Pad14)") (class "Default")
      (node (ref "SW3") (pin "14") (pinfunction "14_14") (pintype "passive"))
    )
    (net (code "411") (name "unconnected-(SW3-Pad15)") (class "Default")
      (node (ref "SW3") (pin "15") (pinfunction "15_15") (pintype "passive"))
    )
    (net (code "412") (name "unconnected-(SW3-Pad16)") (class "Default")
      (node (ref "SW3") (pin "16") (pinfunction "16_16") (pintype "passive"))
    )
    (net (code "413") (name "unconnected-(SW4-Pad1)") (class "Default")
      (node (ref "SW4") (pin "1") (pinfunction "1_1") (pintype "passive"))
    )
    (net (code "414") (name "unconnected-(SW4-Pad2)") (class "Default")
      (node (ref "SW4") (pin "2") (pinfunction "2_2") (pintype "passive"))
    )
    (net (code "415") (name "unconnected-(SW4-Pad3)") (class "Default")
      (node (ref "SW4") (pin "3") (pinfunction "3_3") (pintype "passive"))
    )
    (net (code "416") (name "unconnected-(SW4-Pad4)") (class "Default")
      (node (ref "SW4") (pin "4") (pinfunction "4_4") (pintype "passive"))
    )
    (net (code "417") (name "unconnected-(SW4-Pad5)") (class "Default")
      (node (ref "SW4") (pin "5") (pinfunction "5_5") (pintype "passive"))
    )
    (net (code "418") (name "unconnected-(SW4-Pad6)") (class "Default")
      (node (ref "SW4") (pin "6") (pinfunction "6_6") (pintype "passive"))
    )
    (net (code "419") (name "unconnected-(SW4-Pad7)") (class "Default")
      (node (ref "SW4") (pin "7") (pinfunction "7_7") (pintype "passive"))
    )
    (net (code "420") (name "unconnected-(SW4-Pad8)") (class "Default")
      (node (ref "SW4") (pin "8") (pinfunction "8_8") (pintype "passive"))
    )
    (net (code "421") (name "unconnected-(SW4-Pad9)") (class "Default")
      (node (ref "SW4") (pin "9") (pinfunction "9_9") (pintype "passive"))
    )
    (net (code "422") (name "unconnected-(SW4-Pad10)") (class "Default")
      (node (ref "SW4") (pin "10") (pinfunction "10_10") (pintype "passive"))
    )
    (net (code "423") (name "unconnected-(SW4-Pad11)") (class "Default")
      (node (ref "SW4") (pin "11") (pinfunction "11_11") (pintype "passive"))
    )
    (net (code "424") (name "unconnected-(SW4-Pad12)") (class "Default")
      (node (ref "SW4") (pin "12") (pinfunction "12_12") (pintype "passive"))
    )
    (net (code "425") (name "unconnected-(SW4-Pad13)") (class "Default")
      (node (ref "SW4") (pin "13") (pinfunction "13_13") (pintype "passive"))
    )
    (net (code "426") (name "unconnected-(SW4-Pad14)") (class "Default")
      (node (ref "SW4") (pin "14") (pinfunction "14_14") (pintype "passive"))
    )
    (net (code "427") (name "unconnected-(SW4-Pad15)") (class "Default")
      (node (ref "SW4") (pin "15") (pinfunction "15_15") (pintype "passive"))
    )
    (net (code "428") (name "unconnected-(SW4-Pad16)") (class "Default")
      (node (ref "SW4") (pin "16") (pinfunction "16_16") (pintype "passive"))
    )
  )
)
